# DIY_Keyboard_V1_1.net
KiCad netlist of a schematic drawn in EAGLE
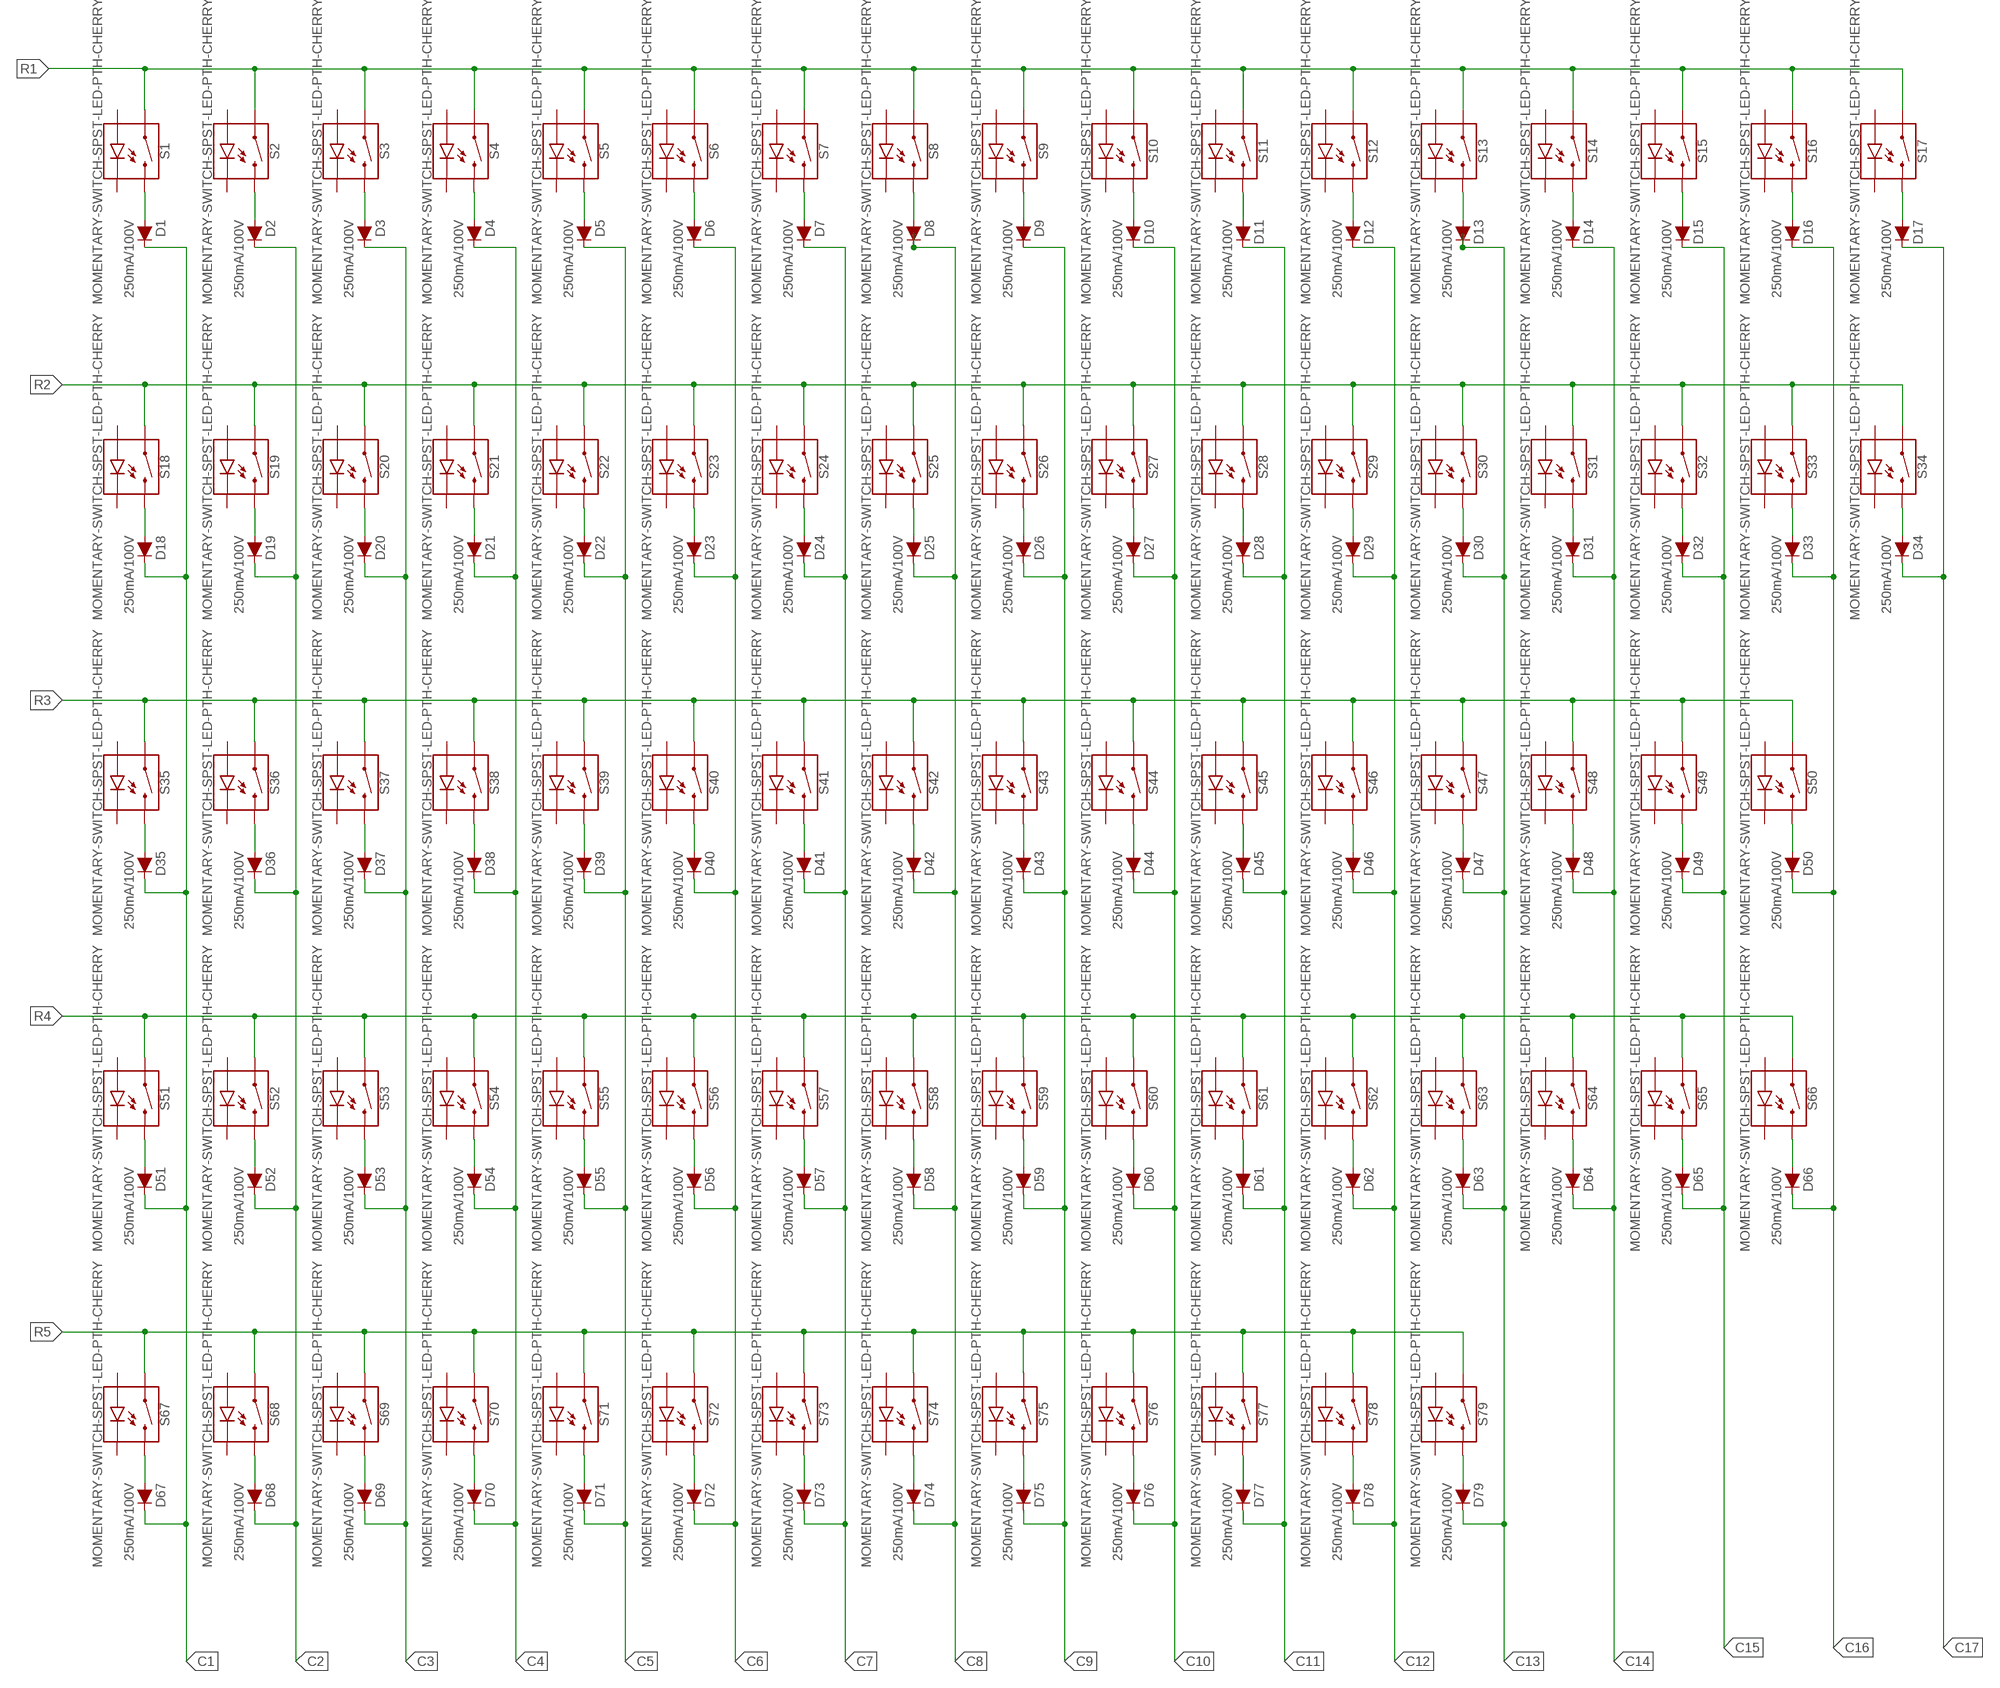
[diagram p0: schematic, sheet 1, part 1 of 2]
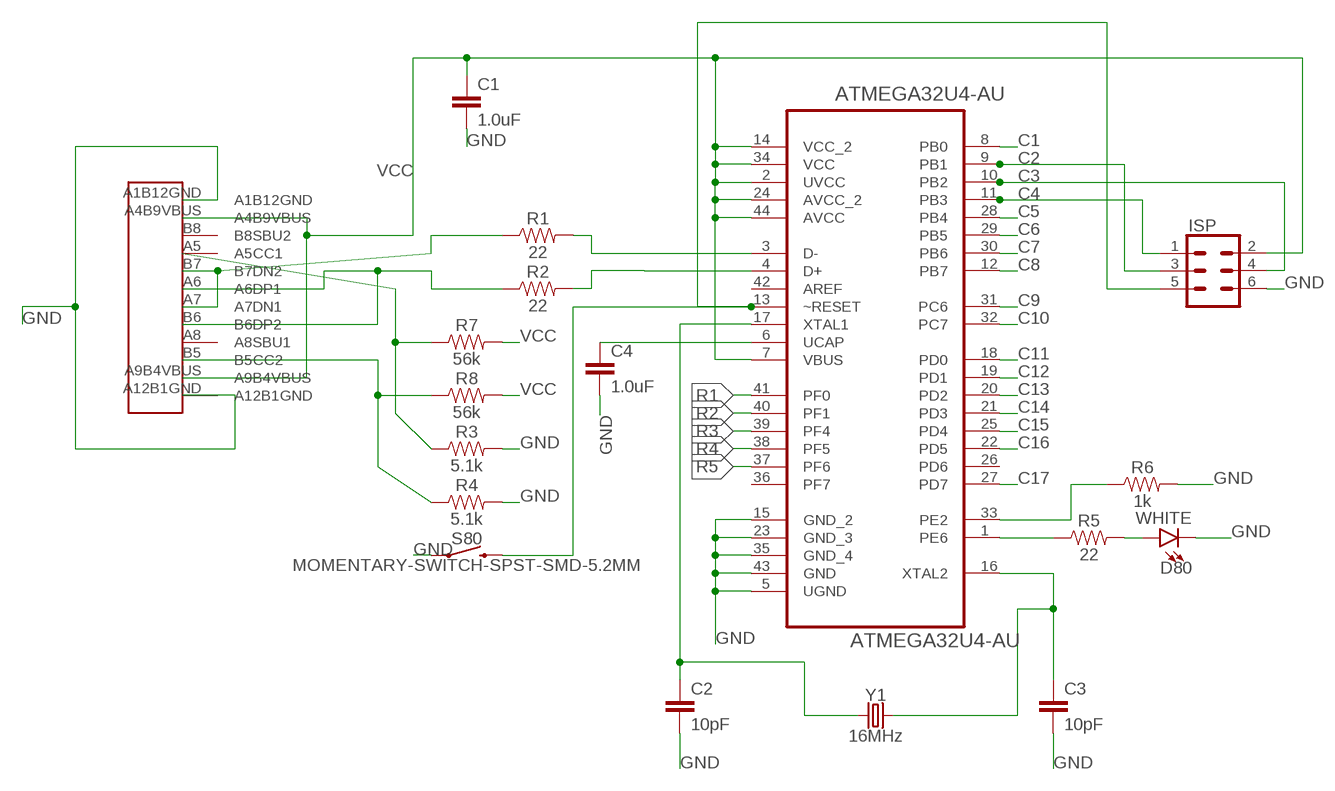
[diagram p1: schematic, sheet 1, part 2 of 2]

(export (version "E")
  (design (tool "Eeschema 10.0.6"))
  (components
    (comp (ref "ATMEGA32U4-AU")
      (value "ATMEGA32U4-AU")
      (footprint "eagle-import:QFP80P1200X1200X120-44N")
      (fields (field (name "MF") "Microchip"))
      (libsource (lib "eagle-import") (part "ATMEGA32U4-AU"))
    )
    (comp (ref "C1")
      (value "1.0uF")
      (footprint "eagle-import:0603")
      (libsource (lib "eagle-import") (part "1.0UF-0603-16V-10%"))
    )
    (comp (ref "C2")
      (value "10pF")
      (footprint "eagle-import:0603")
      (libsource (lib "eagle-import") (part "10PF-0603-50V-5%"))
    )
    (comp (ref "C3")
      (value "10pF")
      (footprint "eagle-import:0603")
      (libsource (lib "eagle-import") (part "10PF-0603-50V-5%"))
    )
    (comp (ref "C4")
      (value "1.0uF")
      (footprint "eagle-import:0603")
      (libsource (lib "eagle-import") (part "1.0UF-0603-16V-10%"))
    )
    (comp (ref "D1")
      (value "250mA/100V")
      (footprint "eagle-import:SOD-323")
      (libsource (lib "eagle-import") (part "DIODE-BAS16J"))
    )
    (comp (ref "D2")
      (value "250mA/100V")
      (footprint "eagle-import:SOD-323")
      (libsource (lib "eagle-import") (part "DIODE-BAS16J"))
    )
    (comp (ref "D3")
      (value "250mA/100V")
      (footprint "eagle-import:SOD-323")
      (libsource (lib "eagle-import") (part "DIODE-BAS16J"))
    )
    (comp (ref "D4")
      (value "250mA/100V")
      (footprint "eagle-import:SOD-323")
      (libsource (lib "eagle-import") (part "DIODE-BAS16J"))
    )
    (comp (ref "D5")
      (value "250mA/100V")
      (footprint "eagle-import:SOD-323")
      (libsource (lib "eagle-import") (part "DIODE-BAS16J"))
    )
    (comp (ref "D6")
      (value "250mA/100V")
      (footprint "eagle-import:SOD-323")
      (libsource (lib "eagle-import") (part "DIODE-BAS16J"))
    )
    (comp (ref "D7")
      (value "250mA/100V")
      (footprint "eagle-import:SOD-323")
      (libsource (lib "eagle-import") (part "DIODE-BAS16J"))
    )
    (comp (ref "D8")
      (value "250mA/100V")
      (footprint "eagle-import:SOD-323")
      (libsource (lib "eagle-import") (part "DIODE-BAS16J"))
    )
    (comp (ref "D9")
      (value "250mA/100V")
      (footprint "eagle-import:SOD-323")
      (libsource (lib "eagle-import") (part "DIODE-BAS16J"))
    )
    (comp (ref "D10")
      (value "250mA/100V")
      (footprint "eagle-import:SOD-323")
      (libsource (lib "eagle-import") (part "DIODE-BAS16J"))
    )
    (comp (ref "D11")
      (value "250mA/100V")
      (footprint "eagle-import:SOD-323")
      (libsource (lib "eagle-import") (part "DIODE-BAS16J"))
    )
    (comp (ref "D12")
      (value "250mA/100V")
      (footprint "eagle-import:SOD-323")
      (libsource (lib "eagle-import") (part "DIODE-BAS16J"))
    )
    (comp (ref "D13")
      (value "250mA/100V")
      (footprint "eagle-import:SOD-323")
      (libsource (lib "eagle-import") (part "DIODE-BAS16J"))
    )
    (comp (ref "D14")
      (value "250mA/100V")
      (footprint "eagle-import:SOD-323")
      (libsource (lib "eagle-import") (part "DIODE-BAS16J"))
    )
    (comp (ref "D15")
      (value "250mA/100V")
      (footprint "eagle-import:SOD-323")
      (libsource (lib "eagle-import") (part "DIODE-BAS16J"))
    )
    (comp (ref "D16")
      (value "250mA/100V")
      (footprint "eagle-import:SOD-323")
      (libsource (lib "eagle-import") (part "DIODE-BAS16J"))
    )
    (comp (ref "D17")
      (value "250mA/100V")
      (footprint "eagle-import:SOD-323")
      (libsource (lib "eagle-import") (part "DIODE-BAS16J"))
    )
    (comp (ref "D18")
      (value "250mA/100V")
      (footprint "eagle-import:SOD-323")
      (libsource (lib "eagle-import") (part "DIODE-BAS16J"))
    )
    (comp (ref "D19")
      (value "250mA/100V")
      (footprint "eagle-import:SOD-323")
      (libsource (lib "eagle-import") (part "DIODE-BAS16J"))
    )
    (comp (ref "D20")
      (value "250mA/100V")
      (footprint "eagle-import:SOD-323")
      (libsource (lib "eagle-import") (part "DIODE-BAS16J"))
    )
    (comp (ref "D21")
      (value "250mA/100V")
      (footprint "eagle-import:SOD-323")
      (libsource (lib "eagle-import") (part "DIODE-BAS16J"))
    )
    (comp (ref "D22")
      (value "250mA/100V")
      (footprint "eagle-import:SOD-323")
      (libsource (lib "eagle-import") (part "DIODE-BAS16J"))
    )
    (comp (ref "D23")
      (value "250mA/100V")
      (footprint "eagle-import:SOD-323")
      (libsource (lib "eagle-import") (part "DIODE-BAS16J"))
    )
    (comp (ref "D24")
      (value "250mA/100V")
      (footprint "eagle-import:SOD-323")
      (libsource (lib "eagle-import") (part "DIODE-BAS16J"))
    )
    (comp (ref "D25")
      (value "250mA/100V")
      (footprint "eagle-import:SOD-323")
      (libsource (lib "eagle-import") (part "DIODE-BAS16J"))
    )
    (comp (ref "D26")
      (value "250mA/100V")
      (footprint "eagle-import:SOD-323")
      (libsource (lib "eagle-import") (part "DIODE-BAS16J"))
    )
    (comp (ref "D27")
      (value "250mA/100V")
      (footprint "eagle-import:SOD-323")
      (libsource (lib "eagle-import") (part "DIODE-BAS16J"))
    )
    (comp (ref "D28")
      (value "250mA/100V")
      (footprint "eagle-import:SOD-323")
      (libsource (lib "eagle-import") (part "DIODE-BAS16J"))
    )
    (comp (ref "D29")
      (value "250mA/100V")
      (footprint "eagle-import:SOD-323")
      (libsource (lib "eagle-import") (part "DIODE-BAS16J"))
    )
    (comp (ref "D30")
      (value "250mA/100V")
      (footprint "eagle-import:SOD-323")
      (libsource (lib "eagle-import") (part "DIODE-BAS16J"))
    )
    (comp (ref "D31")
      (value "250mA/100V")
      (footprint "eagle-import:SOD-323")
      (libsource (lib "eagle-import") (part "DIODE-BAS16J"))
    )
    (comp (ref "D32")
      (value "250mA/100V")
      (footprint "eagle-import:SOD-323")
      (libsource (lib "eagle-import") (part "DIODE-BAS16J"))
    )
    (comp (ref "D33")
      (value "250mA/100V")
      (footprint "eagle-import:SOD-323")
      (libsource (lib "eagle-import") (part "DIODE-BAS16J"))
    )
    (comp (ref "D34")
      (value "250mA/100V")
      (footprint "eagle-import:SOD-323")
      (libsource (lib "eagle-import") (part "DIODE-BAS16J"))
    )
    (comp (ref "D35")
      (value "250mA/100V")
      (footprint "eagle-import:SOD-323")
      (libsource (lib "eagle-import") (part "DIODE-BAS16J"))
    )
    (comp (ref "D36")
      (value "250mA/100V")
      (footprint "eagle-import:SOD-323")
      (libsource (lib "eagle-import") (part "DIODE-BAS16J"))
    )
    (comp (ref "D37")
      (value "250mA/100V")
      (footprint "eagle-import:SOD-323")
      (libsource (lib "eagle-import") (part "DIODE-BAS16J"))
    )
    (comp (ref "D38")
      (value "250mA/100V")
      (footprint "eagle-import:SOD-323")
      (libsource (lib "eagle-import") (part "DIODE-BAS16J"))
    )
    (comp (ref "D39")
      (value "250mA/100V")
      (footprint "eagle-import:SOD-323")
      (libsource (lib "eagle-import") (part "DIODE-BAS16J"))
    )
    (comp (ref "D40")
      (value "250mA/100V")
      (footprint "eagle-import:SOD-323")
      (libsource (lib "eagle-import") (part "DIODE-BAS16J"))
    )
    (comp (ref "D41")
      (value "250mA/100V")
      (footprint "eagle-import:SOD-323")
      (libsource (lib "eagle-import") (part "DIODE-BAS16J"))
    )
    (comp (ref "D42")
      (value "250mA/100V")
      (footprint "eagle-import:SOD-323")
      (libsource (lib "eagle-import") (part "DIODE-BAS16J"))
    )
    (comp (ref "D43")
      (value "250mA/100V")
      (footprint "eagle-import:SOD-323")
      (libsource (lib "eagle-import") (part "DIODE-BAS16J"))
    )
    (comp (ref "D44")
      (value "250mA/100V")
      (footprint "eagle-import:SOD-323")
      (libsource (lib "eagle-import") (part "DIODE-BAS16J"))
    )
    (comp (ref "D45")
      (value "250mA/100V")
      (footprint "eagle-import:SOD-323")
      (libsource (lib "eagle-import") (part "DIODE-BAS16J"))
    )
    (comp (ref "D46")
      (value "250mA/100V")
      (footprint "eagle-import:SOD-323")
      (libsource (lib "eagle-import") (part "DIODE-BAS16J"))
    )
    (comp (ref "D47")
      (value "250mA/100V")
      (footprint "eagle-import:SOD-323")
      (libsource (lib "eagle-import") (part "DIODE-BAS16J"))
    )
    (comp (ref "D48")
      (value "250mA/100V")
      (footprint "eagle-import:SOD-323")
      (libsource (lib "eagle-import") (part "DIODE-BAS16J"))
    )
    (comp (ref "D49")
      (value "250mA/100V")
      (footprint "eagle-import:SOD-323")
      (libsource (lib "eagle-import") (part "DIODE-BAS16J"))
    )
    (comp (ref "D50")
      (value "250mA/100V")
      (footprint "eagle-import:SOD-323")
      (libsource (lib "eagle-import") (part "DIODE-BAS16J"))
    )
    (comp (ref "D51")
      (value "250mA/100V")
      (footprint "eagle-import:SOD-323")
      (libsource (lib "eagle-import") (part "DIODE-BAS16J"))
    )
    (comp (ref "D52")
      (value "250mA/100V")
      (footprint "eagle-import:SOD-323")
      (libsource (lib "eagle-import") (part "DIODE-BAS16J"))
    )
    (comp (ref "D53")
      (value "250mA/100V")
      (footprint "eagle-import:SOD-323")
      (libsource (lib "eagle-import") (part "DIODE-BAS16J"))
    )
    (comp (ref "D54")
      (value "250mA/100V")
      (footprint "eagle-import:SOD-323")
      (libsource (lib "eagle-import") (part "DIODE-BAS16J"))
    )
    (comp (ref "D55")
      (value "250mA/100V")
      (footprint "eagle-import:SOD-323")
      (libsource (lib "eagle-import") (part "DIODE-BAS16J"))
    )
    (comp (ref "D56")
      (value "250mA/100V")
      (footprint "eagle-import:SOD-323")
      (libsource (lib "eagle-import") (part "DIODE-BAS16J"))
    )
    (comp (ref "D57")
      (value "250mA/100V")
      (footprint "eagle-import:SOD-323")
      (libsource (lib "eagle-import") (part "DIODE-BAS16J"))
    )
    (comp (ref "D58")
      (value "250mA/100V")
      (footprint "eagle-import:SOD-323")
      (libsource (lib "eagle-import") (part "DIODE-BAS16J"))
    )
    (comp (ref "D59")
      (value "250mA/100V")
      (footprint "eagle-import:SOD-323")
      (libsource (lib "eagle-import") (part "DIODE-BAS16J"))
    )
    (comp (ref "D60")
      (value "250mA/100V")
      (footprint "eagle-import:SOD-323")
      (libsource (lib "eagle-import") (part "DIODE-BAS16J"))
    )
    (comp (ref "D61")
      (value "250mA/100V")
      (footprint "eagle-import:SOD-323")
      (libsource (lib "eagle-import") (part "DIODE-BAS16J"))
    )
    (comp (ref "D62")
      (value "250mA/100V")
      (footprint "eagle-import:SOD-323")
      (libsource (lib "eagle-import") (part "DIODE-BAS16J"))
    )
    (comp (ref "D63")
      (value "250mA/100V")
      (footprint "eagle-import:SOD-323")
      (libsource (lib "eagle-import") (part "DIODE-BAS16J"))
    )
    (comp (ref "D64")
      (value "250mA/100V")
      (footprint "eagle-import:SOD-323")
      (libsource (lib "eagle-import") (part "DIODE-BAS16J"))
    )
    (comp (ref "D65")
      (value "250mA/100V")
      (footprint "eagle-import:SOD-323")
      (libsource (lib "eagle-import") (part "DIODE-BAS16J"))
    )
    (comp (ref "D66")
      (value "250mA/100V")
      (footprint "eagle-import:SOD-323")
      (libsource (lib "eagle-import") (part "DIODE-BAS16J"))
    )
    (comp (ref "D67")
      (value "250mA/100V")
      (footprint "eagle-import:SOD-323")
      (libsource (lib "eagle-import") (part "DIODE-BAS16J"))
    )
    (comp (ref "D68")
      (value "250mA/100V")
      (footprint "eagle-import:SOD-323")
      (libsource (lib "eagle-import") (part "DIODE-BAS16J"))
    )
    (comp (ref "D69")
      (value "250mA/100V")
      (footprint "eagle-import:SOD-323")
      (libsource (lib "eagle-import") (part "DIODE-BAS16J"))
    )
    (comp (ref "D70")
      (value "250mA/100V")
      (footprint "eagle-import:SOD-323")
      (libsource (lib "eagle-import") (part "DIODE-BAS16J"))
    )
    (comp (ref "D71")
      (value "250mA/100V")
      (footprint "eagle-import:SOD-323")
      (libsource (lib "eagle-import") (part "DIODE-BAS16J"))
    )
    (comp (ref "D72")
      (value "250mA/100V")
      (footprint "eagle-import:SOD-323")
      (libsource (lib "eagle-import") (part "DIODE-BAS16J"))
    )
    (comp (ref "D73")
      (value "250mA/100V")
      (footprint "eagle-import:SOD-323")
      (libsource (lib "eagle-import") (part "DIODE-BAS16J"))
    )
    (comp (ref "D74")
      (value "250mA/100V")
      (footprint "eagle-import:SOD-323")
      (libsource (lib "eagle-import") (part "DIODE-BAS16J"))
    )
    (comp (ref "D75")
      (value "250mA/100V")
      (footprint "eagle-import:SOD-323")
      (libsource (lib "eagle-import") (part "DIODE-BAS16J"))
    )
    (comp (ref "D76")
      (value "250mA/100V")
      (footprint "eagle-import:SOD-323")
      (libsource (lib "eagle-import") (part "DIODE-BAS16J"))
    )
    (comp (ref "D77")
      (value "250mA/100V")
      (footprint "eagle-import:SOD-323")
      (libsource (lib "eagle-import") (part "DIODE-BAS16J"))
    )
    (comp (ref "D78")
      (value "250mA/100V")
      (footprint "eagle-import:SOD-323")
      (libsource (lib "eagle-import") (part "DIODE-BAS16J"))
    )
    (comp (ref "D79")
      (value "250mA/100V")
      (footprint "eagle-import:SOD-323")
      (libsource (lib "eagle-import") (part "DIODE-BAS16J"))
    )
    (comp (ref "D80")
      (value "WHITE")
      (footprint "eagle-import:LED-0603")
      (libsource (lib "eagle-import") (part "LED-WHITE0603"))
    )
    (comp (ref "ISP")
      (value "CONN_03X2FEMALE")
      (footprint "eagle-import:2X3")
      (libsource (lib "eagle-import") (part "CONN_03X2FEMALE"))
    )
    (comp (ref "R1")
      (value "22")
      (footprint "eagle-import:0603")
      (libsource (lib "eagle-import") (part "22OHM-0603-1/10W-1%"))
    )
    (comp (ref "R2")
      (value "22")
      (footprint "eagle-import:0603")
      (libsource (lib "eagle-import") (part "22OHM-0603-1/10W-1%"))
    )
    (comp (ref "R3")
      (value "5.1k")
      (footprint "eagle-import:0603")
      (libsource (lib "eagle-import") (part "56KOHM"))
    )
    (comp (ref "R4")
      (value "5.1k")
      (footprint "eagle-import:0603")
      (libsource (lib "eagle-import") (part "56KOHM"))
    )
    (comp (ref "R5")
      (value "22")
      (footprint "eagle-import:0603")
      (libsource (lib "eagle-import") (part "22OHM-0603-1/10W-1%"))
    )
    (comp (ref "R6")
      (value "1k")
      (footprint "eagle-import:0603")
      (libsource (lib "eagle-import") (part "1KOHM-0603-1/10W-1%"))
    )
    (comp (ref "R7")
      (value "56k")
      (footprint "eagle-import:0603")
      (libsource (lib "eagle-import") (part "56KOHM"))
    )
    (comp (ref "R8")
      (value "56k")
      (footprint "eagle-import:0603")
      (libsource (lib "eagle-import") (part "56KOHM"))
    )
    (comp (ref "S1")
      (value "MOMENTARY-SWITCH-SPST-LED-PTH-CHERRY")
      (footprint "eagle-import:CHERRY-MX-LED")
      (libsource (lib "eagle-import") (part "MOMENTARY-SWITCH-SPST-LED-PTH-CHERRY"))
    )
    (comp (ref "S2")
      (value "MOMENTARY-SWITCH-SPST-LED-PTH-CHERRY")
      (footprint "eagle-import:CHERRY-MX-LED")
      (libsource (lib "eagle-import") (part "MOMENTARY-SWITCH-SPST-LED-PTH-CHERRY"))
    )
    (comp (ref "S3")
      (value "MOMENTARY-SWITCH-SPST-LED-PTH-CHERRY")
      (footprint "eagle-import:CHERRY-MX-LED")
      (libsource (lib "eagle-import") (part "MOMENTARY-SWITCH-SPST-LED-PTH-CHERRY"))
    )
    (comp (ref "S4")
      (value "MOMENTARY-SWITCH-SPST-LED-PTH-CHERRY")
      (footprint "eagle-import:CHERRY-MX-LED")
      (libsource (lib "eagle-import") (part "MOMENTARY-SWITCH-SPST-LED-PTH-CHERRY"))
    )
    (comp (ref "S5")
      (value "MOMENTARY-SWITCH-SPST-LED-PTH-CHERRY")
      (footprint "eagle-import:CHERRY-MX-LED")
      (libsource (lib "eagle-import") (part "MOMENTARY-SWITCH-SPST-LED-PTH-CHERRY"))
    )
    (comp (ref "S6")
      (value "MOMENTARY-SWITCH-SPST-LED-PTH-CHERRY")
      (footprint "eagle-import:CHERRY-MX-LED")
      (libsource (lib "eagle-import") (part "MOMENTARY-SWITCH-SPST-LED-PTH-CHERRY"))
    )
    (comp (ref "S7")
      (value "MOMENTARY-SWITCH-SPST-LED-PTH-CHERRY")
      (footprint "eagle-import:CHERRY-MX-LED")
      (libsource (lib "eagle-import") (part "MOMENTARY-SWITCH-SPST-LED-PTH-CHERRY"))
    )
    (comp (ref "S8")
      (value "MOMENTARY-SWITCH-SPST-LED-PTH-CHERRY")
      (footprint "eagle-import:CHERRY-MX-LED")
      (libsource (lib "eagle-import") (part "MOMENTARY-SWITCH-SPST-LED-PTH-CHERRY"))
    )
    (comp (ref "S9")
      (value "MOMENTARY-SWITCH-SPST-LED-PTH-CHERRY")
      (footprint "eagle-import:CHERRY-MX-LED")
      (libsource (lib "eagle-import") (part "MOMENTARY-SWITCH-SPST-LED-PTH-CHERRY"))
    )
    (comp (ref "S10")
      (value "MOMENTARY-SWITCH-SPST-LED-PTH-CHERRY")
      (footprint "eagle-import:CHERRY-MX-LED")
      (libsource (lib "eagle-import") (part "MOMENTARY-SWITCH-SPST-LED-PTH-CHERRY"))
    )
    (comp (ref "S11")
      (value "MOMENTARY-SWITCH-SPST-LED-PTH-CHERRY")
      (footprint "eagle-import:CHERRY-MX-LED")
      (libsource (lib "eagle-import") (part "MOMENTARY-SWITCH-SPST-LED-PTH-CHERRY"))
    )
    (comp (ref "S12")
      (value "MOMENTARY-SWITCH-SPST-LED-PTH-CHERRY")
      (footprint "eagle-import:CHERRY-MX-LED")
      (libsource (lib "eagle-import") (part "MOMENTARY-SWITCH-SPST-LED-PTH-CHERRY"))
    )
    (comp (ref "S13")
      (value "MOMENTARY-SWITCH-SPST-LED-PTH-CHERRY")
      (footprint "eagle-import:CHERRY-MX-LED")
      (libsource (lib "eagle-import") (part "MOMENTARY-SWITCH-SPST-LED-PTH-CHERRY"))
    )
    (comp (ref "S14")
      (value "MOMENTARY-SWITCH-SPST-LED-PTH-CHERRY")
      (footprint "eagle-import:CHERRY-MX-LED")
      (libsource (lib "eagle-import") (part "MOMENTARY-SWITCH-SPST-LED-PTH-CHERRY"))
    )
    (comp (ref "S15")
      (value "MOMENTARY-SWITCH-SPST-LED-PTH-CHERRY")
      (footprint "eagle-import:CHERRY-MX-LED")
      (libsource (lib "eagle-import") (part "MOMENTARY-SWITCH-SPST-LED-PTH-CHERRY"))
    )
    (comp (ref "S16")
      (value "MOMENTARY-SWITCH-SPST-LED-PTH-CHERRY")
      (footprint "eagle-import:CHERRY-MX-LED")
      (libsource (lib "eagle-import") (part "MOMENTARY-SWITCH-SPST-LED-PTH-CHERRY"))
    )
    (comp (ref "S17")
      (value "MOMENTARY-SWITCH-SPST-LED-PTH-CHERRY")
      (footprint "eagle-import:CHERRY-MX-LED")
      (libsource (lib "eagle-import") (part "MOMENTARY-SWITCH-SPST-LED-PTH-CHERRY"))
    )
    (comp (ref "S18")
      (value "MOMENTARY-SWITCH-SPST-LED-PTH-CHERRY")
      (footprint "eagle-import:CHERRY-MX-LED")
      (libsource (lib "eagle-import") (part "MOMENTARY-SWITCH-SPST-LED-PTH-CHERRY"))
    )
    (comp (ref "S19")
      (value "MOMENTARY-SWITCH-SPST-LED-PTH-CHERRY")
      (footprint "eagle-import:CHERRY-MX-LED")
      (libsource (lib "eagle-import") (part "MOMENTARY-SWITCH-SPST-LED-PTH-CHERRY"))
    )
    (comp (ref "S20")
      (value "MOMENTARY-SWITCH-SPST-LED-PTH-CHERRY")
      (footprint "eagle-import:CHERRY-MX-LED")
      (libsource (lib "eagle-import") (part "MOMENTARY-SWITCH-SPST-LED-PTH-CHERRY"))
    )
    (comp (ref "S21")
      (value "MOMENTARY-SWITCH-SPST-LED-PTH-CHERRY")
      (footprint "eagle-import:CHERRY-MX-LED")
      (libsource (lib "eagle-import") (part "MOMENTARY-SWITCH-SPST-LED-PTH-CHERRY"))
    )
    (comp (ref "S22")
      (value "MOMENTARY-SWITCH-SPST-LED-PTH-CHERRY")
      (footprint "eagle-import:CHERRY-MX-LED")
      (libsource (lib "eagle-import") (part "MOMENTARY-SWITCH-SPST-LED-PTH-CHERRY"))
    )
    (comp (ref "S23")
      (value "MOMENTARY-SWITCH-SPST-LED-PTH-CHERRY")
      (footprint "eagle-import:CHERRY-MX-LED")
      (libsource (lib "eagle-import") (part "MOMENTARY-SWITCH-SPST-LED-PTH-CHERRY"))
    )
    (comp (ref "S24")
      (value "MOMENTARY-SWITCH-SPST-LED-PTH-CHERRY")
      (footprint "eagle-import:CHERRY-MX-LED")
      (libsource (lib "eagle-import") (part "MOMENTARY-SWITCH-SPST-LED-PTH-CHERRY"))
    )
    (comp (ref "S25")
      (value "MOMENTARY-SWITCH-SPST-LED-PTH-CHERRY")
      (footprint "eagle-import:CHERRY-MX-LED")
      (libsource (lib "eagle-import") (part "MOMENTARY-SWITCH-SPST-LED-PTH-CHERRY"))
    )
    (comp (ref "S26")
      (value "MOMENTARY-SWITCH-SPST-LED-PTH-CHERRY")
      (footprint "eagle-import:CHERRY-MX-LED")
      (libsource (lib "eagle-import") (part "MOMENTARY-SWITCH-SPST-LED-PTH-CHERRY"))
    )
    (comp (ref "S27")
      (value "MOMENTARY-SWITCH-SPST-LED-PTH-CHERRY")
      (footprint "eagle-import:CHERRY-MX-LED")
      (libsource (lib "eagle-import") (part "MOMENTARY-SWITCH-SPST-LED-PTH-CHERRY"))
    )
    (comp (ref "S28")
      (value "MOMENTARY-SWITCH-SPST-LED-PTH-CHERRY")
      (footprint "eagle-import:CHERRY-MX-LED")
      (libsource (lib "eagle-import") (part "MOMENTARY-SWITCH-SPST-LED-PTH-CHERRY"))
    )
    (comp (ref "S29")
      (value "MOMENTARY-SWITCH-SPST-LED-PTH-CHERRY")
      (footprint "eagle-import:CHERRY-MX-LED")
      (libsource (lib "eagle-import") (part "MOMENTARY-SWITCH-SPST-LED-PTH-CHERRY"))
    )
    (comp (ref "S30")
      (value "MOMENTARY-SWITCH-SPST-LED-PTH-CHERRY")
      (footprint "eagle-import:CHERRY-MX-LED")
      (libsource (lib "eagle-import") (part "MOMENTARY-SWITCH-SPST-LED-PTH-CHERRY"))
    )
    (comp (ref "S31")
      (value "MOMENTARY-SWITCH-SPST-LED-PTH-CHERRY")
      (footprint "eagle-import:CHERRY-MX-LED")
      (libsource (lib "eagle-import") (part "MOMENTARY-SWITCH-SPST-LED-PTH-CHERRY"))
    )
    (comp (ref "S32")
      (value "MOMENTARY-SWITCH-SPST-LED-PTH-CHERRY")
      (footprint "eagle-import:CHERRY-MX-LED")
      (libsource (lib "eagle-import") (part "MOMENTARY-SWITCH-SPST-LED-PTH-CHERRY"))
    )
    (comp (ref "S33")
      (value "MOMENTARY-SWITCH-SPST-LED-PTH-CHERRY")
      (footprint "eagle-import:CHERRY-MX-LED")
      (libsource (lib "eagle-import") (part "MOMENTARY-SWITCH-SPST-LED-PTH-CHERRY"))
    )
    (comp (ref "S34")
      (value "MOMENTARY-SWITCH-SPST-LED-PTH-CHERRY")
      (footprint "eagle-import:CHERRY-MX-LED")
      (libsource (lib "eagle-import") (part "MOMENTARY-SWITCH-SPST-LED-PTH-CHERRY"))
    )
    (comp (ref "S35")
      (value "MOMENTARY-SWITCH-SPST-LED-PTH-CHERRY")
      (footprint "eagle-import:CHERRY-MX-LED")
      (libsource (lib "eagle-import") (part "MOMENTARY-SWITCH-SPST-LED-PTH-CHERRY"))
    )
    (comp (ref "S36")
      (value "MOMENTARY-SWITCH-SPST-LED-PTH-CHERRY")
      (footprint "eagle-import:CHERRY-MX-LED")
      (libsource (lib "eagle-import") (part "MOMENTARY-SWITCH-SPST-LED-PTH-CHERRY"))
    )
    (comp (ref "S37")
      (value "MOMENTARY-SWITCH-SPST-LED-PTH-CHERRY")
      (footprint "eagle-import:CHERRY-MX-LED")
      (libsource (lib "eagle-import") (part "MOMENTARY-SWITCH-SPST-LED-PTH-CHERRY"))
    )
    (comp (ref "S38")
      (value "MOMENTARY-SWITCH-SPST-LED-PTH-CHERRY")
      (footprint "eagle-import:CHERRY-MX-LED")
      (libsource (lib "eagle-import") (part "MOMENTARY-SWITCH-SPST-LED-PTH-CHERRY"))
    )
    (comp (ref "S39")
      (value "MOMENTARY-SWITCH-SPST-LED-PTH-CHERRY")
      (footprint "eagle-import:CHERRY-MX-LED")
      (libsource (lib "eagle-import") (part "MOMENTARY-SWITCH-SPST-LED-PTH-CHERRY"))
    )
    (comp (ref "S40")
      (value "MOMENTARY-SWITCH-SPST-LED-PTH-CHERRY")
      (footprint "eagle-import:CHERRY-MX-LED")
      (libsource (lib "eagle-import") (part "MOMENTARY-SWITCH-SPST-LED-PTH-CHERRY"))
    )
    (comp (ref "S41")
      (value "MOMENTARY-SWITCH-SPST-LED-PTH-CHERRY")
      (footprint "eagle-import:CHERRY-MX-LED")
      (libsource (lib "eagle-import") (part "MOMENTARY-SWITCH-SPST-LED-PTH-CHERRY"))
    )
    (comp (ref "S42")
      (value "MOMENTARY-SWITCH-SPST-LED-PTH-CHERRY")
      (footprint "eagle-import:CHERRY-MX-LED")
      (libsource (lib "eagle-import") (part "MOMENTARY-SWITCH-SPST-LED-PTH-CHERRY"))
    )
    (comp (ref "S43")
      (value "MOMENTARY-SWITCH-SPST-LED-PTH-CHERRY")
      (footprint "eagle-import:CHERRY-MX-LED")
      (libsource (lib "eagle-import") (part "MOMENTARY-SWITCH-SPST-LED-PTH-CHERRY"))
    )
    (comp (ref "S44")
      (value "MOMENTARY-SWITCH-SPST-LED-PTH-CHERRY")
      (footprint "eagle-import:CHERRY-MX-LED")
      (libsource (lib "eagle-import") (part "MOMENTARY-SWITCH-SPST-LED-PTH-CHERRY"))
    )
    (comp (ref "S45")
      (value "MOMENTARY-SWITCH-SPST-LED-PTH-CHERRY")
      (footprint "eagle-import:CHERRY-MX-LED")
      (libsource (lib "eagle-import") (part "MOMENTARY-SWITCH-SPST-LED-PTH-CHERRY"))
    )
    (comp (ref "S46")
      (value "MOMENTARY-SWITCH-SPST-LED-PTH-CHERRY")
      (footprint "eagle-import:CHERRY-MX-LED")
      (libsource (lib "eagle-import") (part "MOMENTARY-SWITCH-SPST-LED-PTH-CHERRY"))
    )
    (comp (ref "S47")
      (value "MOMENTARY-SWITCH-SPST-LED-PTH-CHERRY")
      (footprint "eagle-import:CHERRY-MX-LED")
      (libsource (lib "eagle-import") (part "MOMENTARY-SWITCH-SPST-LED-PTH-CHERRY"))
    )
    (comp (ref "S48")
      (value "MOMENTARY-SWITCH-SPST-LED-PTH-CHERRY")
      (footprint "eagle-import:CHERRY-MX-LED")
      (libsource (lib "eagle-import") (part "MOMENTARY-SWITCH-SPST-LED-PTH-CHERRY"))
    )
    (comp (ref "S49")
      (value "MOMENTARY-SWITCH-SPST-LED-PTH-CHERRY")
      (footprint "eagle-import:CHERRY-MX-LED")
      (libsource (lib "eagle-import") (part "MOMENTARY-SWITCH-SPST-LED-PTH-CHERRY"))
    )
    (comp (ref "S50")
      (value "MOMENTARY-SWITCH-SPST-LED-PTH-CHERRY")
      (footprint "eagle-import:CHERRY-MX-LED")
      (libsource (lib "eagle-import") (part "MOMENTARY-SWITCH-SPST-LED-PTH-CHERRY"))
    )
    (comp (ref "S51")
      (value "MOMENTARY-SWITCH-SPST-LED-PTH-CHERRY")
      (footprint "eagle-import:CHERRY-MX-LED")
      (libsource (lib "eagle-import") (part "MOMENTARY-SWITCH-SPST-LED-PTH-CHERRY"))
    )
    (comp (ref "S52")
      (value "MOMENTARY-SWITCH-SPST-LED-PTH-CHERRY")
      (footprint "eagle-import:CHERRY-MX-LED")
      (libsource (lib "eagle-import") (part "MOMENTARY-SWITCH-SPST-LED-PTH-CHERRY"))
    )
    (comp (ref "S53")
      (value "MOMENTARY-SWITCH-SPST-LED-PTH-CHERRY")
      (footprint "eagle-import:CHERRY-MX-LED")
      (libsource (lib "eagle-import") (part "MOMENTARY-SWITCH-SPST-LED-PTH-CHERRY"))
    )
    (comp (ref "S54")
      (value "MOMENTARY-SWITCH-SPST-LED-PTH-CHERRY")
      (footprint "eagle-import:CHERRY-MX-LED")
      (libsource (lib "eagle-import") (part "MOMENTARY-SWITCH-SPST-LED-PTH-CHERRY"))
    )
    (comp (ref "S55")
      (value "MOMENTARY-SWITCH-SPST-LED-PTH-CHERRY")
      (footprint "eagle-import:CHERRY-MX-LED")
      (libsource (lib "eagle-import") (part "MOMENTARY-SWITCH-SPST-LED-PTH-CHERRY"))
    )
    (comp (ref "S56")
      (value "MOMENTARY-SWITCH-SPST-LED-PTH-CHERRY")
      (footprint "eagle-import:CHERRY-MX-LED")
      (libsource (lib "eagle-import") (part "MOMENTARY-SWITCH-SPST-LED-PTH-CHERRY"))
    )
    (comp (ref "S57")
      (value "MOMENTARY-SWITCH-SPST-LED-PTH-CHERRY")
      (footprint "eagle-import:CHERRY-MX-LED")
      (libsource (lib "eagle-import") (part "MOMENTARY-SWITCH-SPST-LED-PTH-CHERRY"))
    )
    (comp (ref "S58")
      (value "MOMENTARY-SWITCH-SPST-LED-PTH-CHERRY")
      (footprint "eagle-import:CHERRY-MX-LED")
      (libsource (lib "eagle-import") (part "MOMENTARY-SWITCH-SPST-LED-PTH-CHERRY"))
    )
    (comp (ref "S59")
      (value "MOMENTARY-SWITCH-SPST-LED-PTH-CHERRY")
      (footprint "eagle-import:CHERRY-MX-LED")
      (libsource (lib "eagle-import") (part "MOMENTARY-SWITCH-SPST-LED-PTH-CHERRY"))
    )
    (comp (ref "S60")
      (value "MOMENTARY-SWITCH-SPST-LED-PTH-CHERRY")
      (footprint "eagle-import:CHERRY-MX-LED")
      (libsource (lib "eagle-import") (part "MOMENTARY-SWITCH-SPST-LED-PTH-CHERRY"))
    )
    (comp (ref "S61")
      (value "MOMENTARY-SWITCH-SPST-LED-PTH-CHERRY")
      (footprint "eagle-import:CHERRY-MX-LED")
      (libsource (lib "eagle-import") (part "MOMENTARY-SWITCH-SPST-LED-PTH-CHERRY"))
    )
    (comp (ref "S62")
      (value "MOMENTARY-SWITCH-SPST-LED-PTH-CHERRY")
      (footprint "eagle-import:CHERRY-MX-LED")
      (libsource (lib "eagle-import") (part "MOMENTARY-SWITCH-SPST-LED-PTH-CHERRY"))
    )
    (comp (ref "S63")
      (value "MOMENTARY-SWITCH-SPST-LED-PTH-CHERRY")
      (footprint "eagle-import:CHERRY-MX-LED")
      (libsource (lib "eagle-import") (part "MOMENTARY-SWITCH-SPST-LED-PTH-CHERRY"))
    )
    (comp (ref "S64")
      (value "MOMENTARY-SWITCH-SPST-LED-PTH-CHERRY")
      (footprint "eagle-import:CHERRY-MX-LED")
      (libsource (lib "eagle-import") (part "MOMENTARY-SWITCH-SPST-LED-PTH-CHERRY"))
    )
    (comp (ref "S65")
      (value "MOMENTARY-SWITCH-SPST-LED-PTH-CHERRY")
      (footprint "eagle-import:CHERRY-MX-LED")
      (libsource (lib "eagle-import") (part "MOMENTARY-SWITCH-SPST-LED-PTH-CHERRY"))
    )
    (comp (ref "S66")
      (value "MOMENTARY-SWITCH-SPST-LED-PTH-CHERRY")
      (footprint "eagle-import:CHERRY-MX-LED")
      (libsource (lib "eagle-import") (part "MOMENTARY-SWITCH-SPST-LED-PTH-CHERRY"))
    )
    (comp (ref "S67")
      (value "MOMENTARY-SWITCH-SPST-LED-PTH-CHERRY")
      (footprint "eagle-import:CHERRY-MX-LED")
      (libsource (lib "eagle-import") (part "MOMENTARY-SWITCH-SPST-LED-PTH-CHERRY"))
    )
    (comp (ref "S68")
      (value "MOMENTARY-SWITCH-SPST-LED-PTH-CHERRY")
      (footprint "eagle-import:CHERRY-MX-LED")
      (libsource (lib "eagle-import") (part "MOMENTARY-SWITCH-SPST-LED-PTH-CHERRY"))
    )
    (comp (ref "S69")
      (value "MOMENTARY-SWITCH-SPST-LED-PTH-CHERRY")
      (footprint "eagle-import:CHERRY-MX-LED")
      (libsource (lib "eagle-import") (part "MOMENTARY-SWITCH-SPST-LED-PTH-CHERRY"))
    )
    (comp (ref "S70")
      (value "MOMENTARY-SWITCH-SPST-LED-PTH-CHERRY")
      (footprint "eagle-import:CHERRY-MX-LED")
      (libsource (lib "eagle-import") (part "MOMENTARY-SWITCH-SPST-LED-PTH-CHERRY"))
    )
    (comp (ref "S71")
      (value "MOMENTARY-SWITCH-SPST-LED-PTH-CHERRY")
      (footprint "eagle-import:CHERRY-MX-LED")
      (libsource (lib "eagle-import") (part "MOMENTARY-SWITCH-SPST-LED-PTH-CHERRY"))
    )
    (comp (ref "S72")
      (value "MOMENTARY-SWITCH-SPST-LED-PTH-CHERRY")
      (footprint "eagle-import:CHERRY-MX-LED")
      (libsource (lib "eagle-import") (part "MOMENTARY-SWITCH-SPST-LED-PTH-CHERRY"))
    )
    (comp (ref "S73")
      (value "MOMENTARY-SWITCH-SPST-LED-PTH-CHERRY")
      (footprint "eagle-import:CHERRY-MX-LED")
      (libsource (lib "eagle-import") (part "MOMENTARY-SWITCH-SPST-LED-PTH-CHERRY"))
    )
    (comp (ref "S74")
      (value "MOMENTARY-SWITCH-SPST-LED-PTH-CHERRY")
      (footprint "eagle-import:CHERRY-MX-LED")
      (libsource (lib "eagle-import") (part "MOMENTARY-SWITCH-SPST-LED-PTH-CHERRY"))
    )
    (comp (ref "S75")
      (value "MOMENTARY-SWITCH-SPST-LED-PTH-CHERRY")
      (footprint "eagle-import:CHERRY-MX-LED")
      (libsource (lib "eagle-import") (part "MOMENTARY-SWITCH-SPST-LED-PTH-CHERRY"))
    )
    (comp (ref "S76")
      (value "MOMENTARY-SWITCH-SPST-LED-PTH-CHERRY")
      (footprint "eagle-import:CHERRY-MX-LED")
      (libsource (lib "eagle-import") (part "MOMENTARY-SWITCH-SPST-LED-PTH-CHERRY"))
    )
    (comp (ref "S77")
      (value "MOMENTARY-SWITCH-SPST-LED-PTH-CHERRY")
      (footprint "eagle-import:CHERRY-MX-LED")
      (libsource (lib "eagle-import") (part "MOMENTARY-SWITCH-SPST-LED-PTH-CHERRY"))
    )
    (comp (ref "S78")
      (value "MOMENTARY-SWITCH-SPST-LED-PTH-CHERRY")
      (footprint "eagle-import:CHERRY-MX-LED")
      (libsource (lib "eagle-import") (part "MOMENTARY-SWITCH-SPST-LED-PTH-CHERRY"))
    )
    (comp (ref "S79")
      (value "MOMENTARY-SWITCH-SPST-LED-PTH-CHERRY")
      (footprint "eagle-import:CHERRY-MX-LED")
      (libsource (lib "eagle-import") (part "MOMENTARY-SWITCH-SPST-LED-PTH-CHERRY"))
    )
    (comp (ref "S80")
      (value "MOMENTARY-SWITCH-SPST-SMD-5.2MM")
      (footprint "eagle-import:TACTILE_SWITCH_SMD_5.2MM")
      (libsource (lib "eagle-import") (part "MOMENTARY-SWITCH-SPST-SMD-5.2MM"))
    )
    (comp (ref "U$1")
      (value "USB_TYPE_C")
      (footprint "eagle-import:USB_TYPE_C")
      (libsource (lib "eagle-import") (part "USB_TYPE_C"))
    )
    (comp (ref "Y1")
      (value "16MHz")
      (footprint "eagle-import:CRYSTAL-SMD-5X3.2-4PAD")
      (libsource (lib "eagle-import") (part "CRYSTAL-16MHZSMD-5X3.2"))
    )
  )
  (nets
    (net (code "1") (name "/GND") (class "Default")
      (node (ref "ATMEGA32U4-AU") (pin "15") (pinfunction "GND_2_15") (pintype "passive"))
      (node (ref "ATMEGA32U4-AU") (pin "23") (pinfunction "GND_3_23") (pintype "passive"))
      (node (ref "ATMEGA32U4-AU") (pin "35") (pinfunction "GND_4_35") (pintype "passive"))
      (node (ref "ATMEGA32U4-AU") (pin "43") (pinfunction "GND_43") (pintype "passive"))
      (node (ref "ATMEGA32U4-AU") (pin "5") (pinfunction "UGND_5") (pintype "passive"))
      (node (ref "C1") (pin "2") (pinfunction "2_2") (pintype "passive"))
      (node (ref "C2") (pin "2") (pinfunction "2_2") (pintype "passive"))
      (node (ref "C3") (pin "2") (pinfunction "2_2") (pintype "passive"))
      (node (ref "C4") (pin "2") (pinfunction "2_2") (pintype "passive"))
      (node (ref "D80") (pin "C") (pinfunction "C_C") (pintype "passive"))
      (node (ref "ISP") (pin "6") (pinfunction "6_6") (pintype "bidirectional"))
      (node (ref "R3") (pin "2") (pinfunction "2_2") (pintype "passive"))
      (node (ref "R4") (pin "2") (pinfunction "2_2") (pintype "passive"))
      (node (ref "R6") (pin "2") (pinfunction "2_2") (pintype "passive"))
      (node (ref "S80") (pin "1") (pinfunction "1_1") (pintype "passive"))
      (node (ref "U$1") (pin "A12B1GND") (pinfunction "A12B1GND_A12B1GND") (pintype "bidirectional"))
      (node (ref "U$1") (pin "A1B12GND") (pinfunction "A1B12GND_A1B12GND") (pintype "bidirectional"))
    )
    (net (code "2") (name "/VCC") (class "Default")
      (node (ref "ATMEGA32U4-AU") (pin "14") (pinfunction "VCC_2_14") (pintype "power_in"))
      (node (ref "ATMEGA32U4-AU") (pin "2") (pinfunction "UVCC_2") (pintype "power_in"))
      (node (ref "ATMEGA32U4-AU") (pin "24") (pinfunction "AVCC_2_24") (pintype "power_in"))
      (node (ref "ATMEGA32U4-AU") (pin "34") (pinfunction "VCC_34") (pintype "power_in"))
      (node (ref "ATMEGA32U4-AU") (pin "44") (pinfunction "AVCC_44") (pintype "power_in"))
      (node (ref "ATMEGA32U4-AU") (pin "7") (pinfunction "VBUS_7") (pintype "input"))
      (node (ref "C1") (pin "1") (pinfunction "1_1") (pintype "passive"))
      (node (ref "ISP") (pin "2") (pinfunction "2_2") (pintype "bidirectional"))
      (node (ref "R7") (pin "2") (pinfunction "2_2") (pintype "passive"))
      (node (ref "R8") (pin "2") (pinfunction "2_2") (pintype "passive"))
      (node (ref "U$1") (pin "A4B9VBUS") (pinfunction "A4B9VBUS_A4B9VBUS") (pintype "bidirectional"))
      (node (ref "U$1") (pin "A9B4VBUS") (pinfunction "A9B4VBUS_A9B4VBUS") (pintype "bidirectional"))
    )
    (net (code "3") (name "C1") (class "Default")
      (node (ref "ATMEGA32U4-AU") (pin "8") (pinfunction "PB0_8") (pintype "bidirectional"))
      (node (ref "D1") (pin "C") (pinfunction "C_C") (pintype "passive"))
      (node (ref "D18") (pin "C") (pinfunction "C_C") (pintype "passive"))
      (node (ref "D35") (pin "C") (pinfunction "C_C") (pintype "passive"))
      (node (ref "D51") (pin "C") (pinfunction "C_C") (pintype "passive"))
      (node (ref "D67") (pin "C") (pinfunction "C_C") (pintype "passive"))
    )
    (net (code "4") (name "C2") (class "Default")
      (node (ref "ATMEGA32U4-AU") (pin "9") (pinfunction "PB1_9") (pintype "bidirectional"))
      (node (ref "D19") (pin "C") (pinfunction "C_C") (pintype "passive"))
      (node (ref "D2") (pin "C") (pinfunction "C_C") (pintype "passive"))
      (node (ref "D36") (pin "C") (pinfunction "C_C") (pintype "passive"))
      (node (ref "D52") (pin "C") (pinfunction "C_C") (pintype "passive"))
      (node (ref "D68") (pin "C") (pinfunction "C_C") (pintype "passive"))
      (node (ref "ISP") (pin "3") (pinfunction "3_3") (pintype "bidirectional"))
    )
    (net (code "5") (name "C3") (class "Default")
      (node (ref "ATMEGA32U4-AU") (pin "10") (pinfunction "PB2_10") (pintype "bidirectional"))
      (node (ref "D20") (pin "C") (pinfunction "C_C") (pintype "passive"))
      (node (ref "D3") (pin "C") (pinfunction "C_C") (pintype "passive"))
      (node (ref "D37") (pin "C") (pinfunction "C_C") (pintype "passive"))
      (node (ref "D53") (pin "C") (pinfunction "C_C") (pintype "passive"))
      (node (ref "D69") (pin "C") (pinfunction "C_C") (pintype "passive"))
      (node (ref "ISP") (pin "4") (pinfunction "4_4") (pintype "bidirectional"))
    )
    (net (code "6") (name "C4") (class "Default")
      (node (ref "ATMEGA32U4-AU") (pin "11") (pinfunction "PB3_11") (pintype "bidirectional"))
      (node (ref "D21") (pin "C") (pinfunction "C_C") (pintype "passive"))
      (node (ref "D38") (pin "C") (pinfunction "C_C") (pintype "passive"))
      (node (ref "D4") (pin "C") (pinfunction "C_C") (pintype "passive"))
      (node (ref "D54") (pin "C") (pinfunction "C_C") (pintype "passive"))
      (node (ref "D70") (pin "C") (pinfunction "C_C") (pintype "passive"))
      (node (ref "ISP") (pin "1") (pinfunction "1_1") (pintype "bidirectional"))
    )
    (net (code "7") (name "C5") (class "Default")
      (node (ref "ATMEGA32U4-AU") (pin "28") (pinfunction "PB4_28") (pintype "bidirectional"))
      (node (ref "D22") (pin "C") (pinfunction "C_C") (pintype "passive"))
      (node (ref "D39") (pin "C") (pinfunction "C_C") (pintype "passive"))
      (node (ref "D5") (pin "C") (pinfunction "C_C") (pintype "passive"))
      (node (ref "D55") (pin "C") (pinfunction "C_C") (pintype "passive"))
      (node (ref "D71") (pin "C") (pinfunction "C_C") (pintype "passive"))
    )
    (net (code "8") (name "C6") (class "Default")
      (node (ref "ATMEGA32U4-AU") (pin "29") (pinfunction "PB5_29") (pintype "bidirectional"))
      (node (ref "D23") (pin "C") (pinfunction "C_C") (pintype "passive"))
      (node (ref "D40") (pin "C") (pinfunction "C_C") (pintype "passive"))
      (node (ref "D56") (pin "C") (pinfunction "C_C") (pintype "passive"))
      (node (ref "D6") (pin "C") (pinfunction "C_C") (pintype "passive"))
      (node (ref "D72") (pin "C") (pinfunction "C_C") (pintype "passive"))
    )
    (net (code "9") (name "C7") (class "Default")
      (node (ref "ATMEGA32U4-AU") (pin "30") (pinfunction "PB6_30") (pintype "bidirectional"))
      (node (ref "D24") (pin "C") (pinfunction "C_C") (pintype "passive"))
      (node (ref "D41") (pin "C") (pinfunction "C_C") (pintype "passive"))
      (node (ref "D57") (pin "C") (pinfunction "C_C") (pintype "passive"))
      (node (ref "D7") (pin "C") (pinfunction "C_C") (pintype "passive"))
      (node (ref "D73") (pin "C") (pinfunction "C_C") (pintype "passive"))
    )
    (net (code "10") (name "C8") (class "Default")
      (node (ref "ATMEGA32U4-AU") (pin "12") (pinfunction "PB7_12") (pintype "bidirectional"))
      (node (ref "D25") (pin "C") (pinfunction "C_C") (pintype "passive"))
      (node (ref "D42") (pin "C") (pinfunction "C_C") (pintype "passive"))
      (node (ref "D58") (pin "C") (pinfunction "C_C") (pintype "passive"))
      (node (ref "D74") (pin "C") (pinfunction "C_C") (pintype "passive"))
      (node (ref "D8") (pin "C") (pinfunction "C_C") (pintype "passive"))
    )
    (net (code "11") (name "C9") (class "Default")
      (node (ref "ATMEGA32U4-AU") (pin "31") (pinfunction "PC6_31") (pintype "bidirectional"))
      (node (ref "D26") (pin "C") (pinfunction "C_C") (pintype "passive"))
      (node (ref "D43") (pin "C") (pinfunction "C_C") (pintype "passive"))
      (node (ref "D59") (pin "C") (pinfunction "C_C") (pintype "passive"))
      (node (ref "D75") (pin "C") (pinfunction "C_C") (pintype "passive"))
      (node (ref "D9") (pin "C") (pinfunction "C_C") (pintype "passive"))
    )
    (net (code "12") (name "C10") (class "Default")
      (node (ref "ATMEGA32U4-AU") (pin "32") (pinfunction "PC7_32") (pintype "bidirectional"))
      (node (ref "D10") (pin "C") (pinfunction "C_C") (pintype "passive"))
      (node (ref "D27") (pin "C") (pinfunction "C_C") (pintype "passive"))
      (node (ref "D44") (pin "C") (pinfunction "C_C") (pintype "passive"))
      (node (ref "D60") (pin "C") (pinfunction "C_C") (pintype "passive"))
      (node (ref "D76") (pin "C") (pinfunction "C_C") (pintype "passive"))
    )
    (net (code "13") (name "C11") (class "Default")
      (node (ref "ATMEGA32U4-AU") (pin "18") (pinfunction "PD0_18") (pintype "bidirectional"))
      (node (ref "D11") (pin "C") (pinfunction "C_C") (pintype "passive"))
      (node (ref "D28") (pin "C") (pinfunction "C_C") (pintype "passive"))
      (node (ref "D45") (pin "C") (pinfunction "C_C") (pintype "passive"))
      (node (ref "D61") (pin "C") (pinfunction "C_C") (pintype "passive"))
      (node (ref "D77") (pin "C") (pinfunction "C_C") (pintype "passive"))
    )
    (net (code "14") (name "C12") (class "Default")
      (node (ref "ATMEGA32U4-AU") (pin "19") (pinfunction "PD1_19") (pintype "bidirectional"))
      (node (ref "D12") (pin "C") (pinfunction "C_C") (pintype "passive"))
      (node (ref "D29") (pin "C") (pinfunction "C_C") (pintype "passive"))
      (node (ref "D46") (pin "C") (pinfunction "C_C") (pintype "passive"))
      (node (ref "D62") (pin "C") (pinfunction "C_C") (pintype "passive"))
      (node (ref "D78") (pin "C") (pinfunction "C_C") (pintype "passive"))
    )
    (net (code "15") (name "C13") (class "Default")
      (node (ref "ATMEGA32U4-AU") (pin "20") (pinfunction "PD2_20") (pintype "bidirectional"))
      (node (ref "D13") (pin "C") (pinfunction "C_C") (pintype "passive"))
      (node (ref "D30") (pin "C") (pinfunction "C_C") (pintype "passive"))
      (node (ref "D47") (pin "C") (pinfunction "C_C") (pintype "passive"))
      (node (ref "D63") (pin "C") (pinfunction "C_C") (pintype "passive"))
      (node (ref "D79") (pin "C") (pinfunction "C_C") (pintype "passive"))
    )
    (net (code "16") (name "C14") (class "Default")
      (node (ref "ATMEGA32U4-AU") (pin "21") (pinfunction "PD3_21") (pintype "bidirectional"))
      (node (ref "D14") (pin "C") (pinfunction "C_C") (pintype "passive"))
      (node (ref "D31") (pin "C") (pinfunction "C_C") (pintype "passive"))
      (node (ref "D48") (pin "C") (pinfunction "C_C") (pintype "passive"))
      (node (ref "D64") (pin "C") (pinfunction "C_C") (pintype "passive"))
    )
    (net (code "17") (name "C15") (class "Default")
      (node (ref "ATMEGA32U4-AU") (pin "25") (pinfunction "PD4_25") (pintype "bidirectional"))
      (node (ref "D15") (pin "C") (pinfunction "C_C") (pintype "passive"))
      (node (ref "D32") (pin "C") (pinfunction "C_C") (pintype "passive"))
      (node (ref "D49") (pin "C") (pinfunction "C_C") (pintype "passive"))
      (node (ref "D65") (pin "C") (pinfunction "C_C") (pintype "passive"))
    )
    (net (code "18") (name "C16") (class "Default")
      (node (ref "ATMEGA32U4-AU") (pin "22") (pinfunction "PD5_22") (pintype "bidirectional"))
      (node (ref "D16") (pin "C") (pinfunction "C_C") (pintype "passive"))
      (node (ref "D33") (pin "C") (pinfunction "C_C") (pintype "passive"))
      (node (ref "D50") (pin "C") (pinfunction "C_C") (pintype "passive"))
      (node (ref "D66") (pin "C") (pinfunction "C_C") (pintype "passive"))
    )
    (net (code "19") (name "C17") (class "Default")
      (node (ref "ATMEGA32U4-AU") (pin "27") (pinfunction "PD7_27") (pintype "bidirectional"))
      (node (ref "D17") (pin "C") (pinfunction "C_C") (pintype "passive"))
      (node (ref "D34") (pin "C") (pinfunction "C_C") (pintype "passive"))
    )
    (net (code "20") (name "Net-(ATMEGA32U4-AU-D+)") (class "Default")
      (node (ref "ATMEGA32U4-AU") (pin "4") (pinfunction "D+_4") (pintype "passive"))
      (node (ref "R2") (pin "2") (pinfunction "2_2") (pintype "passive"))
    )
    (net (code "21") (name "Net-(ATMEGA32U4-AU-D-)") (class "Default")
      (node (ref "ATMEGA32U4-AU") (pin "3") (pinfunction "D-_3") (pintype "passive"))
      (node (ref "R1") (pin "2") (pinfunction "2_2") (pintype "passive"))
    )
    (net (code "22") (name "Net-(ATMEGA32U4-AU-PE2)") (class "Default")
      (node (ref "ATMEGA32U4-AU") (pin "33") (pinfunction "PE2_33") (pintype "bidirectional"))
      (node (ref "R6") (pin "1") (pinfunction "1_1") (pintype "passive"))
    )
    (net (code "23") (name "Net-(ATMEGA32U4-AU-PE6)") (class "Default")
      (node (ref "ATMEGA32U4-AU") (pin "1") (pinfunction "PE6_1") (pintype "bidirectional"))
      (node (ref "R5") (pin "1") (pinfunction "1_1") (pintype "passive"))
    )
    (net (code "24") (name "Net-(ATMEGA32U4-AU-UCAP)") (class "Default")
      (node (ref "ATMEGA32U4-AU") (pin "6") (pinfunction "UCAP_6") (pintype "power_in"))
      (node (ref "C4") (pin "1") (pinfunction "1_1") (pintype "passive"))
    )
    (net (code "25") (name "Net-(ATMEGA32U4-AU-XTAL1)") (class "Default")
      (node (ref "ATMEGA32U4-AU") (pin "17") (pinfunction "XTAL1_17") (pintype "input"))
      (node (ref "C2") (pin "1") (pinfunction "1_1") (pintype "passive"))
      (node (ref "Y1") (pin "1") (pinfunction "1_1") (pintype "passive"))
    )
    (net (code "26") (name "Net-(ATMEGA32U4-AU-XTAL2)") (class "Default")
      (node (ref "ATMEGA32U4-AU") (pin "16") (pinfunction "XTAL2_16") (pintype "output"))
      (node (ref "C3") (pin "1") (pinfunction "1_1") (pintype "passive"))
      (node (ref "Y1") (pin "3") (pinfunction "2_3") (pintype "passive"))
    )
    (net (code "27") (name "Net-(ATMEGA32U4-AU-~{RESET})") (class "Default")
      (node (ref "ATMEGA32U4-AU") (pin "13") (pinfunction "~{RESET}_13") (pintype "input"))
      (node (ref "ISP") (pin "5") (pinfunction "5_5") (pintype "bidirectional"))
      (node (ref "S80") (pin "3") (pinfunction "2_3") (pintype "passive"))
    )
    (net (code "28") (name "Net-(D80-PadA)") (class "Default")
      (node (ref "D80") (pin "A") (pinfunction "A_A") (pintype "passive"))
      (node (ref "R5") (pin "2") (pinfunction "2_2") (pintype "passive"))
    )
    (net (code "29") (name "Net-(S1-2)") (class "Default")
      (node (ref "D1") (pin "A") (pinfunction "A_A") (pintype "passive"))
      (node (ref "S1") (pin "S2") (pinfunction "2_S2") (pintype "passive"))
    )
    (net (code "30") (name "Net-(S2-2)") (class "Default")
      (node (ref "D2") (pin "A") (pinfunction "A_A") (pintype "passive"))
      (node (ref "S2") (pin "S2") (pinfunction "2_S2") (pintype "passive"))
    )
    (net (code "31") (name "Net-(S3-2)") (class "Default")
      (node (ref "D3") (pin "A") (pinfunction "A_A") (pintype "passive"))
      (node (ref "S3") (pin "S2") (pinfunction "2_S2") (pintype "passive"))
    )
    (net (code "32") (name "Net-(S4-2)") (class "Default")
      (node (ref "D4") (pin "A") (pinfunction "A_A") (pintype "passive"))
      (node (ref "S4") (pin "S2") (pinfunction "2_S2") (pintype "passive"))
    )
    (net (code "33") (name "Net-(S5-2)") (class "Default")
      (node (ref "D5") (pin "A") (pinfunction "A_A") (pintype "passive"))
      (node (ref "S5") (pin "S2") (pinfunction "2_S2") (pintype "passive"))
    )
    (net (code "34") (name "Net-(S6-2)") (class "Default")
      (node (ref "D6") (pin "A") (pinfunction "A_A") (pintype "passive"))
      (node (ref "S6") (pin "S2") (pinfunction "2_S2") (pintype "passive"))
    )
    (net (code "35") (name "Net-(S7-2)") (class "Default")
      (node (ref "D7") (pin "A") (pinfunction "A_A") (pintype "passive"))
      (node (ref "S7") (pin "S2") (pinfunction "2_S2") (pintype "passive"))
    )
    (net (code "36") (name "Net-(S8-2)") (class "Default")
      (node (ref "D8") (pin "A") (pinfunction "A_A") (pintype "passive"))
      (node (ref "S8") (pin "S2") (pinfunction "2_S2") (pintype "passive"))
    )
    (net (code "37") (name "Net-(S9-2)") (class "Default")
      (node (ref "D9") (pin "A") (pinfunction "A_A") (pintype "passive"))
      (node (ref "S9") (pin "S2") (pinfunction "2_S2") (pintype "passive"))
    )
    (net (code "38") (name "Net-(S10-2)") (class "Default")
      (node (ref "D10") (pin "A") (pinfunction "A_A") (pintype "passive"))
      (node (ref "S10") (pin "S2") (pinfunction "2_S2") (pintype "passive"))
    )
    (net (code "39") (name "Net-(S11-2)") (class "Default")
      (node (ref "D11") (pin "A") (pinfunction "A_A") (pintype "passive"))
      (node (ref "S11") (pin "S2") (pinfunction "2_S2") (pintype "passive"))
    )
    (net (code "40") (name "Net-(S12-2)") (class "Default")
      (node (ref "D12") (pin "A") (pinfunction "A_A") (pintype "passive"))
      (node (ref "S12") (pin "S2") (pinfunction "2_S2") (pintype "passive"))
    )
    (net (code "41") (name "Net-(S13-2)") (class "Default")
      (node (ref "D13") (pin "A") (pinfunction "A_A") (pintype "passive"))
      (node (ref "S13") (pin "S2") (pinfunction "2_S2") (pintype "passive"))
    )
    (net (code "42") (name "Net-(S14-2)") (class "Default")
      (node (ref "D14") (pin "A") (pinfunction "A_A") (pintype "passive"))
      (node (ref "S14") (pin "S2") (pinfunction "2_S2") (pintype "passive"))
    )
    (net (code "43") (name "Net-(S15-2)") (class "Default")
      (node (ref "D15") (pin "A") (pinfunction "A_A") (pintype "passive"))
      (node (ref "S15") (pin "S2") (pinfunction "2_S2") (pintype "passive"))
    )
    (net (code "44") (name "Net-(S16-2)") (class "Default")
      (node (ref "D16") (pin "A") (pinfunction "A_A") (pintype "passive"))
      (node (ref "S16") (pin "S2") (pinfunction "2_S2") (pintype "passive"))
    )
    (net (code "45") (name "Net-(S17-2)") (class "Default")
      (node (ref "D17") (pin "A") (pinfunction "A_A") (pintype "passive"))
      (node (ref "S17") (pin "S2") (pinfunction "2_S2") (pintype "passive"))
    )
    (net (code "46") (name "Net-(S18-2)") (class "Default")
      (node (ref "D18") (pin "A") (pinfunction "A_A") (pintype "passive"))
      (node (ref "S18") (pin "S2") (pinfunction "2_S2") (pintype "passive"))
    )
    (net (code "47") (name "Net-(S19-2)") (class "Default")
      (node (ref "D19") (pin "A") (pinfunction "A_A") (pintype "passive"))
      (node (ref "S19") (pin "S2") (pinfunction "2_S2") (pintype "passive"))
    )
    (net (code "48") (name "Net-(S20-2)") (class "Default")
      (node (ref "D20") (pin "A") (pinfunction "A_A") (pintype "passive"))
      (node (ref "S20") (pin "S2") (pinfunction "2_S2") (pintype "passive"))
    )
    (net (code "49") (name "Net-(S21-2)") (class "Default")
      (node (ref "D21") (pin "A") (pinfunction "A_A") (pintype "passive"))
      (node (ref "S21") (pin "S2") (pinfunction "2_S2") (pintype "passive"))
    )
    (net (code "50") (name "Net-(S22-2)") (class "Default")
      (node (ref "D22") (pin "A") (pinfunction "A_A") (pintype "passive"))
      (node (ref "S22") (pin "S2") (pinfunction "2_S2") (pintype "passive"))
    )
    (net (code "51") (name "Net-(S23-2)") (class "Default")
      (node (ref "D23") (pin "A") (pinfunction "A_A") (pintype "passive"))
      (node (ref "S23") (pin "S2") (pinfunction "2_S2") (pintype "passive"))
    )
    (net (code "52") (name "Net-(S24-2)") (class "Default")
      (node (ref "D24") (pin "A") (pinfunction "A_A") (pintype "passive"))
      (node (ref "S24") (pin "S2") (pinfunction "2_S2") (pintype "passive"))
    )
    (net (code "53") (name "Net-(S25-2)") (class "Default")
      (node (ref "D25") (pin "A") (pinfunction "A_A") (pintype "passive"))
      (node (ref "S25") (pin "S2") (pinfunction "2_S2") (pintype "passive"))
    )
    (net (code "54") (name "Net-(S26-2)") (class "Default")
      (node (ref "D26") (pin "A") (pinfunction "A_A") (pintype "passive"))
      (node (ref "S26") (pin "S2") (pinfunction "2_S2") (pintype "passive"))
    )
    (net (code "55") (name "Net-(S27-2)") (class "Default")
      (node (ref "D27") (pin "A") (pinfunction "A_A") (pintype "passive"))
      (node (ref "S27") (pin "S2") (pinfunction "2_S2") (pintype "passive"))
    )
    (net (code "56") (name "Net-(S28-2)") (class "Default")
      (node (ref "D28") (pin "A") (pinfunction "A_A") (pintype "passive"))
      (node (ref "S28") (pin "S2") (pinfunction "2_S2") (pintype "passive"))
    )
    (net (code "57") (name "Net-(S29-2)") (class "Default")
      (node (ref "D29") (pin "A") (pinfunction "A_A") (pintype "passive"))
      (node (ref "S29") (pin "S2") (pinfunction "2_S2") (pintype "passive"))
    )
    (net (code "58") (name "Net-(S30-2)") (class "Default")
      (node (ref "D30") (pin "A") (pinfunction "A_A") (pintype "passive"))
      (node (ref "S30") (pin "S2") (pinfunction "2_S2") (pintype "passive"))
    )
    (net (code "59") (name "Net-(S31-2)") (class "Default")
      (node (ref "D31") (pin "A") (pinfunction "A_A") (pintype "passive"))
      (node (ref "S31") (pin "S2") (pinfunction "2_S2") (pintype "passive"))
    )
    (net (code "60") (name "Net-(S32-2)") (class "Default")
      (node (ref "D32") (pin "A") (pinfunction "A_A") (pintype "passive"))
      (node (ref "S32") (pin "S2") (pinfunction "2_S2") (pintype "passive"))
    )
    (net (code "61") (name "Net-(S33-2)") (class "Default")
      (node (ref "D33") (pin "A") (pinfunction "A_A") (pintype "passive"))
      (node (ref "S33") (pin "S2") (pinfunction "2_S2") (pintype "passive"))
    )
    (net (code "62") (name "Net-(S34-2)") (class "Default")
      (node (ref "D34") (pin "A") (pinfunction "A_A") (pintype "passive"))
      (node (ref "S34") (pin "S2") (pinfunction "2_S2") (pintype "passive"))
    )
    (net (code "63") (name "Net-(S35-2)") (class "Default")
      (node (ref "D35") (pin "A") (pinfunction "A_A") (pintype "passive"))
      (node (ref "S35") (pin "S2") (pinfunction "2_S2") (pintype "passive"))
    )
    (net (code "64") (name "Net-(S36-2)") (class "Default")
      (node (ref "D36") (pin "A") (pinfunction "A_A") (pintype "passive"))
      (node (ref "S36") (pin "S2") (pinfunction "2_S2") (pintype "passive"))
    )
    (net (code "65") (name "Net-(S37-2)") (class "Default")
      (node (ref "D37") (pin "A") (pinfunction "A_A") (pintype "passive"))
      (node (ref "S37") (pin "S2") (pinfunction "2_S2") (pintype "passive"))
    )
    (net (code "66") (name "Net-(S38-2)") (class "Default")
      (node (ref "D38") (pin "A") (pinfunction "A_A") (pintype "passive"))
      (node (ref "S38") (pin "S2") (pinfunction "2_S2") (pintype "passive"))
    )
    (net (code "67") (name "Net-(S39-2)") (class "Default")
      (node (ref "D39") (pin "A") (pinfunction "A_A") (pintype "passive"))
      (node (ref "S39") (pin "S2") (pinfunction "2_S2") (pintype "passive"))
    )
    (net (code "68") (name "Net-(S40-2)") (class "Default")
      (node (ref "D40") (pin "A") (pinfunction "A_A") (pintype "passive"))
      (node (ref "S40") (pin "S2") (pinfunction "2_S2") (pintype "passive"))
    )
    (net (code "69") (name "Net-(S41-2)") (class "Default")
      (node (ref "D41") (pin "A") (pinfunction "A_A") (pintype "passive"))
      (node (ref "S41") (pin "S2") (pinfunction "2_S2") (pintype "passive"))
    )
    (net (code "70") (name "Net-(S42-2)") (class "Default")
      (node (ref "D42") (pin "A") (pinfunction "A_A") (pintype "passive"))
      (node (ref "S42") (pin "S2") (pinfunction "2_S2") (pintype "passive"))
    )
    (net (code "71") (name "Net-(S43-2)") (class "Default")
      (node (ref "D43") (pin "A") (pinfunction "A_A") (pintype "passive"))
      (node (ref "S43") (pin "S2") (pinfunction "2_S2") (pintype "passive"))
    )
    (net (code "72") (name "Net-(S44-2)") (class "Default")
      (node (ref "D44") (pin "A") (pinfunction "A_A") (pintype "passive"))
      (node (ref "S44") (pin "S2") (pinfunction "2_S2") (pintype "passive"))
    )
    (net (code "73") (name "Net-(S45-2)") (class "Default")
      (node (ref "D45") (pin "A") (pinfunction "A_A") (pintype "passive"))
      (node (ref "S45") (pin "S2") (pinfunction "2_S2") (pintype "passive"))
    )
    (net (code "74") (name "Net-(S46-2)") (class "Default")
      (node (ref "D46") (pin "A") (pinfunction "A_A") (pintype "passive"))
      (node (ref "S46") (pin "S2") (pinfunction "2_S2") (pintype "passive"))
    )
    (net (code "75") (name "Net-(S47-2)") (class "Default")
      (node (ref "D47") (pin "A") (pinfunction "A_A") (pintype "passive"))
      (node (ref "S47") (pin "S2") (pinfunction "2_S2") (pintype "passive"))
    )
    (net (code "76") (name "Net-(S48-2)") (class "Default")
      (node (ref "D48") (pin "A") (pinfunction "A_A") (pintype "passive"))
      (node (ref "S48") (pin "S2") (pinfunction "2_S2") (pintype "passive"))
    )
    (net (code "77") (name "Net-(S49-2)") (class "Default")
      (node (ref "D49") (pin "A") (pinfunction "A_A") (pintype "passive"))
      (node (ref "S49") (pin "S2") (pinfunction "2_S2") (pintype "passive"))
    )
    (net (code "78") (name "Net-(S50-2)") (class "Default")
      (node (ref "D50") (pin "A") (pinfunction "A_A") (pintype "passive"))
      (node (ref "S50") (pin "S2") (pinfunction "2_S2") (pintype "passive"))
    )
    (net (code "79") (name "Net-(S51-2)") (class "Default")
      (node (ref "D51") (pin "A") (pinfunction "A_A") (pintype "passive"))
      (node (ref "S51") (pin "S2") (pinfunction "2_S2") (pintype "passive"))
    )
    (net (code "80") (name "Net-(S52-2)") (class "Default")
      (node (ref "D52") (pin "A") (pinfunction "A_A") (pintype "passive"))
      (node (ref "S52") (pin "S2") (pinfunction "2_S2") (pintype "passive"))
    )
    (net (code "81") (name "Net-(S53-2)") (class "Default")
      (node (ref "D53") (pin "A") (pinfunction "A_A") (pintype "passive"))
      (node (ref "S53") (pin "S2") (pinfunction "2_S2") (pintype "passive"))
    )
    (net (code "82") (name "Net-(S54-2)") (class "Default")
      (node (ref "D54") (pin "A") (pinfunction "A_A") (pintype "passive"))
      (node (ref "S54") (pin "S2") (pinfunction "2_S2") (pintype "passive"))
    )
    (net (code "83") (name "Net-(S55-2)") (class "Default")
      (node (ref "D55") (pin "A") (pinfunction "A_A") (pintype "passive"))
      (node (ref "S55") (pin "S2") (pinfunction "2_S2") (pintype "passive"))
    )
    (net (code "84") (name "Net-(S56-2)") (class "Default")
      (node (ref "D56") (pin "A") (pinfunction "A_A") (pintype "passive"))
      (node (ref "S56") (pin "S2") (pinfunction "2_S2") (pintype "passive"))
    )
    (net (code "85") (name "Net-(S57-2)") (class "Default")
      (node (ref "D57") (pin "A") (pinfunction "A_A") (pintype "passive"))
      (node (ref "S57") (pin "S2") (pinfunction "2_S2") (pintype "passive"))
    )
    (net (code "86") (name "Net-(S58-2)") (class "Default")
      (node (ref "D58") (pin "A") (pinfunction "A_A") (pintype "passive"))
      (node (ref "S58") (pin "S2") (pinfunction "2_S2") (pintype "passive"))
    )
    (net (code "87") (name "Net-(S59-2)") (class "Default")
      (node (ref "D59") (pin "A") (pinfunction "A_A") (pintype "passive"))
      (node (ref "S59") (pin "S2") (pinfunction "2_S2") (pintype "passive"))
    )
    (net (code "88") (name "Net-(S60-2)") (class "Default")
      (node (ref "D60") (pin "A") (pinfunction "A_A") (pintype "passive"))
      (node (ref "S60") (pin "S2") (pinfunction "2_S2") (pintype "passive"))
    )
    (net (code "89") (name "Net-(S61-2)") (class "Default")
      (node (ref "D61") (pin "A") (pinfunction "A_A") (pintype "passive"))
      (node (ref "S61") (pin "S2") (pinfunction "2_S2") (pintype "passive"))
    )
    (net (code "90") (name "Net-(S62-2)") (class "Default")
      (node (ref "D62") (pin "A") (pinfunction "A_A") (pintype "passive"))
      (node (ref "S62") (pin "S2") (pinfunction "2_S2") (pintype "passive"))
    )
    (net (code "91") (name "Net-(S63-2)") (class "Default")
      (node (ref "D63") (pin "A") (pinfunction "A_A") (pintype "passive"))
      (node (ref "S63") (pin "S2") (pinfunction "2_S2") (pintype "passive"))
    )
    (net (code "92") (name "Net-(S64-2)") (class "Default")
      (node (ref "D64") (pin "A") (pinfunction "A_A") (pintype "passive"))
      (node (ref "S64") (pin "S2") (pinfunction "2_S2") (pintype "passive"))
    )
    (net (code "93") (name "Net-(S65-2)") (class "Default")
      (node (ref "D65") (pin "A") (pinfunction "A_A") (pintype "passive"))
      (node (ref "S65") (pin "S2") (pinfunction "2_S2") (pintype "passive"))
    )
    (net (code "94") (name "Net-(S66-2)") (class "Default")
      (node (ref "D66") (pin "A") (pinfunction "A_A") (pintype "passive"))
      (node (ref "S66") (pin "S2") (pinfunction "2_S2") (pintype "passive"))
    )
    (net (code "95") (name "Net-(S67-2)") (class "Default")
      (node (ref "D67") (pin "A") (pinfunction "A_A") (pintype "passive"))
      (node (ref "S67") (pin "S2") (pinfunction "2_S2") (pintype "passive"))
    )
    (net (code "96") (name "Net-(S68-2)") (class "Default")
      (node (ref "D68") (pin "A") (pinfunction "A_A") (pintype "passive"))
      (node (ref "S68") (pin "S2") (pinfunction "2_S2") (pintype "passive"))
    )
    (net (code "97") (name "Net-(S69-2)") (class "Default")
      (node (ref "D69") (pin "A") (pinfunction "A_A") (pintype "passive"))
      (node (ref "S69") (pin "S2") (pinfunction "2_S2") (pintype "passive"))
    )
    (net (code "98") (name "Net-(S70-2)") (class "Default")
      (node (ref "D70") (pin "A") (pinfunction "A_A") (pintype "passive"))
      (node (ref "S70") (pin "S2") (pinfunction "2_S2") (pintype "passive"))
    )
    (net (code "99") (name "Net-(S71-2)") (class "Default")
      (node (ref "D71") (pin "A") (pinfunction "A_A") (pintype "passive"))
      (node (ref "S71") (pin "S2") (pinfunction "2_S2") (pintype "passive"))
    )
    (net (code "100") (name "Net-(S72-2)") (class "Default")
      (node (ref "D72") (pin "A") (pinfunction "A_A") (pintype "passive"))
      (node (ref "S72") (pin "S2") (pinfunction "2_S2") (pintype "passive"))
    )
    (net (code "101") (name "Net-(S73-2)") (class "Default")
      (node (ref "D73") (pin "A") (pinfunction "A_A") (pintype "passive"))
      (node (ref "S73") (pin "S2") (pinfunction "2_S2") (pintype "passive"))
    )
    (net (code "102") (name "Net-(S74-2)") (class "Default")
      (node (ref "D74") (pin "A") (pinfunction "A_A") (pintype "passive"))
      (node (ref "S74") (pin "S2") (pinfunction "2_S2") (pintype "passive"))
    )
    (net (code "103") (name "Net-(S75-2)") (class "Default")
      (node (ref "D75") (pin "A") (pinfunction "A_A") (pintype "passive"))
      (node (ref "S75") (pin "S2") (pinfunction "2_S2") (pintype "passive"))
    )
    (net (code "104") (name "Net-(S76-2)") (class "Default")
      (node (ref "D76") (pin "A") (pinfunction "A_A") (pintype "passive"))
      (node (ref "S76") (pin "S2") (pinfunction "2_S2") (pintype "passive"))
    )
    (net (code "105") (name "Net-(S77-2)") (class "Default")
      (node (ref "D77") (pin "A") (pinfunction "A_A") (pintype "passive"))
      (node (ref "S77") (pin "S2") (pinfunction "2_S2") (pintype "passive"))
    )
    (net (code "106") (name "Net-(S78-2)") (class "Default")
      (node (ref "D78") (pin "A") (pinfunction "A_A") (pintype "passive"))
      (node (ref "S78") (pin "S2") (pinfunction "2_S2") (pintype "passive"))
    )
    (net (code "107") (name "Net-(S79-2)") (class "Default")
      (node (ref "D79") (pin "A") (pinfunction "A_A") (pintype "passive"))
      (node (ref "S79") (pin "S2") (pinfunction "2_S2") (pintype "passive"))
    )
    (net (code "108") (name "Net-(U$1-A5CC1)") (class "Default")
      (node (ref "R3") (pin "1") (pinfunction "1_1") (pintype "passive"))
      (node (ref "R7") (pin "1") (pinfunction "1_1") (pintype "passive"))
      (node (ref "U$1") (pin "A5") (pinfunction "A5CC1_A5") (pintype "bidirectional"))
    )
    (net (code "109") (name "Net-(U$1-A6DP1)") (class "Default")
      (node (ref "R2") (pin "1") (pinfunction "1_1") (pintype "passive"))
      (node (ref "U$1") (pin "A6") (pinfunction "A6DP1_A6") (pintype "bidirectional"))
      (node (ref "U$1") (pin "B6") (pinfunction "B6DP2_B6") (pintype "bidirectional"))
    )
    (net (code "110") (name "Net-(U$1-A7DN1)") (class "Default")
      (node (ref "R1") (pin "1") (pinfunction "1_1") (pintype "passive"))
      (node (ref "U$1") (pin "A7") (pinfunction "A7DN1_A7") (pintype "bidirectional"))
      (node (ref "U$1") (pin "B7") (pinfunction "B7DN2_B7") (pintype "bidirectional"))
    )
    (net (code "111") (name "Net-(U$1-B5CC2)") (class "Default")
      (node (ref "R4") (pin "1") (pinfunction "1_1") (pintype "passive"))
      (node (ref "R8") (pin "1") (pinfunction "1_1") (pintype "passive"))
      (node (ref "U$1") (pin "B5") (pinfunction "B5CC2_B5") (pintype "bidirectional"))
    )
    (net (code "112") (name "R1") (class "Default")
      (node (ref "ATMEGA32U4-AU") (pin "41") (pinfunction "PF0_41") (pintype "bidirectional"))
      (node (ref "S1") (pin "S1") (pinfunction "1_S1") (pintype "passive"))
      (node (ref "S10") (pin "S1") (pinfunction "1_S1") (pintype "passive"))
      (node (ref "S11") (pin "S1") (pinfunction "1_S1") (pintype "passive"))
      (node (ref "S12") (pin "S1") (pinfunction "1_S1") (pintype "passive"))
      (node (ref "S13") (pin "S1") (pinfunction "1_S1") (pintype "passive"))
      (node (ref "S14") (pin "S1") (pinfunction "1_S1") (pintype "passive"))
      (node (ref "S15") (pin "S1") (pinfunction "1_S1") (pintype "passive"))
      (node (ref "S16") (pin "S1") (pinfunction "1_S1") (pintype "passive"))
      (node (ref "S17") (pin "S1") (pinfunction "1_S1") (pintype "passive"))
      (node (ref "S2") (pin "S1") (pinfunction "1_S1") (pintype "passive"))
      (node (ref "S3") (pin "S1") (pinfunction "1_S1") (pintype "passive"))
      (node (ref "S4") (pin "S1") (pinfunction "1_S1") (pintype "passive"))
      (node (ref "S5") (pin "S1") (pinfunction "1_S1") (pintype "passive"))
      (node (ref "S6") (pin "S1") (pinfunction "1_S1") (pintype "passive"))
      (node (ref "S7") (pin "S1") (pinfunction "1_S1") (pintype "passive"))
      (node (ref "S8") (pin "S1") (pinfunction "1_S1") (pintype "passive"))
      (node (ref "S9") (pin "S1") (pinfunction "1_S1") (pintype "passive"))
    )
    (net (code "113") (name "R2") (class "Default")
      (node (ref "ATMEGA32U4-AU") (pin "40") (pinfunction "PF1_40") (pintype "bidirectional"))
      (node (ref "S18") (pin "S1") (pinfunction "1_S1") (pintype "passive"))
      (node (ref "S19") (pin "S1") (pinfunction "1_S1") (pintype "passive"))
      (node (ref "S20") (pin "S1") (pinfunction "1_S1") (pintype "passive"))
      (node (ref "S21") (pin "S1") (pinfunction "1_S1") (pintype "passive"))
      (node (ref "S22") (pin "S1") (pinfunction "1_S1") (pintype "passive"))
      (node (ref "S23") (pin "S1") (pinfunction "1_S1") (pintype "passive"))
      (node (ref "S24") (pin "S1") (pinfunction "1_S1") (pintype "passive"))
      (node (ref "S25") (pin "S1") (pinfunction "1_S1") (pintype "passive"))
      (node (ref "S26") (pin "S1") (pinfunction "1_S1") (pintype "passive"))
      (node (ref "S27") (pin "S1") (pinfunction "1_S1") (pintype "passive"))
      (node (ref "S28") (pin "S1") (pinfunction "1_S1") (pintype "passive"))
      (node (ref "S29") (pin "S1") (pinfunction "1_S1") (pintype "passive"))
      (node (ref "S30") (pin "S1") (pinfunction "1_S1") (pintype "passive"))
      (node (ref "S31") (pin "S1") (pinfunction "1_S1") (pintype "passive"))
      (node (ref "S32") (pin "S1") (pinfunction "1_S1") (pintype "passive"))
      (node (ref "S33") (pin "S1") (pinfunction "1_S1") (pintype "passive"))
      (node (ref "S34") (pin "S1") (pinfunction "1_S1") (pintype "passive"))
    )
    (net (code "114") (name "R3") (class "Default")
      (node (ref "ATMEGA32U4-AU") (pin "39") (pinfunction "PF4_39") (pintype "bidirectional"))
      (node (ref "S35") (pin "S1") (pinfunction "1_S1") (pintype "passive"))
      (node (ref "S36") (pin "S1") (pinfunction "1_S1") (pintype "passive"))
      (node (ref "S37") (pin "S1") (pinfunction "1_S1") (pintype "passive"))
      (node (ref "S38") (pin "S1") (pinfunction "1_S1") (pintype "passive"))
      (node (ref "S39") (pin "S1") (pinfunction "1_S1") (pintype "passive"))
      (node (ref "S40") (pin "S1") (pinfunction "1_S1") (pintype "passive"))
      (node (ref "S41") (pin "S1") (pinfunction "1_S1") (pintype "passive"))
      (node (ref "S42") (pin "S1") (pinfunction "1_S1") (pintype "passive"))
      (node (ref "S43") (pin "S1") (pinfunction "1_S1") (pintype "passive"))
      (node (ref "S44") (pin "S1") (pinfunction "1_S1") (pintype "passive"))
      (node (ref "S45") (pin "S1") (pinfunction "1_S1") (pintype "passive"))
      (node (ref "S46") (pin "S1") (pinfunction "1_S1") (pintype "passive"))
      (node (ref "S47") (pin "S1") (pinfunction "1_S1") (pintype "passive"))
      (node (ref "S48") (pin "S1") (pinfunction "1_S1") (pintype "passive"))
      (node (ref "S49") (pin "S1") (pinfunction "1_S1") (pintype "passive"))
      (node (ref "S50") (pin "S1") (pinfunction "1_S1") (pintype "passive"))
    )
    (net (code "115") (name "R4") (class "Default")
      (node (ref "ATMEGA32U4-AU") (pin "38") (pinfunction "PF5_38") (pintype "bidirectional"))
      (node (ref "S51") (pin "S1") (pinfunction "1_S1") (pintype "passive"))
      (node (ref "S52") (pin "S1") (pinfunction "1_S1") (pintype "passive"))
      (node (ref "S53") (pin "S1") (pinfunction "1_S1") (pintype "passive"))
      (node (ref "S54") (pin "S1") (pinfunction "1_S1") (pintype "passive"))
      (node (ref "S55") (pin "S1") (pinfunction "1_S1") (pintype "passive"))
      (node (ref "S56") (pin "S1") (pinfunction "1_S1") (pintype "passive"))
      (node (ref "S57") (pin "S1") (pinfunction "1_S1") (pintype "passive"))
      (node (ref "S58") (pin "S1") (pinfunction "1_S1") (pintype "passive"))
      (node (ref "S59") (pin "S1") (pinfunction "1_S1") (pintype "passive"))
      (node (ref "S60") (pin "S1") (pinfunction "1_S1") (pintype "passive"))
      (node (ref "S61") (pin "S1") (pinfunction "1_S1") (pintype "passive"))
      (node (ref "S62") (pin "S1") (pinfunction "1_S1") (pintype "passive"))
      (node (ref "S63") (pin "S1") (pinfunction "1_S1") (pintype "passive"))
      (node (ref "S64") (pin "S1") (pinfunction "1_S1") (pintype "passive"))
      (node (ref "S65") (pin "S1") (pinfunction "1_S1") (pintype "passive"))
      (node (ref "S66") (pin "S1") (pinfunction "1_S1") (pintype "passive"))
    )
    (net (code "116") (name "R5") (class "Default")
      (node (ref "ATMEGA32U4-AU") (pin "37") (pinfunction "PF6_37") (pintype "bidirectional"))
      (node (ref "S67") (pin "S1") (pinfunction "1_S1") (pintype "passive"))
      (node (ref "S68") (pin "S1") (pinfunction "1_S1") (pintype "passive"))
      (node (ref "S69") (pin "S1") (pinfunction "1_S1") (pintype "passive"))
      (node (ref "S70") (pin "S1") (pinfunction "1_S1") (pintype "passive"))
      (node (ref "S71") (pin "S1") (pinfunction "1_S1") (pintype "passive"))
      (node (ref "S72") (pin "S1") (pinfunction "1_S1") (pintype "passive"))
      (node (ref "S73") (pin "S1") (pinfunction "1_S1") (pintype "passive"))
      (node (ref "S74") (pin "S1") (pinfunction "1_S1") (pintype "passive"))
      (node (ref "S75") (pin "S1") (pinfunction "1_S1") (pintype "passive"))
      (node (ref "S76") (pin "S1") (pinfunction "1_S1") (pintype "passive"))
      (node (ref "S77") (pin "S1") (pinfunction "1_S1") (pintype "passive"))
      (node (ref "S78") (pin "S1") (pinfunction "1_S1") (pintype "passive"))
      (node (ref "S79") (pin "S1") (pinfunction "1_S1") (pintype "passive"))
    )
    (net (code "117") (name "unconnected-(ATMEGA32U4-AU-AREF-Pad42)") (class "Default")
      (node (ref "ATMEGA32U4-AU") (pin "42") (pinfunction "AREF_42") (pintype "input"))
    )
    (net (code "118") (name "unconnected-(ATMEGA32U4-AU-PD6-Pad26)") (class "Default")
      (node (ref "ATMEGA32U4-AU") (pin "26") (pinfunction "PD6_26") (pintype "bidirectional"))
    )
    (net (code "119") (name "unconnected-(ATMEGA32U4-AU-PF7-Pad36)") (class "Default")
      (node (ref "ATMEGA32U4-AU") (pin "36") (pinfunction "PF7_36") (pintype "bidirectional"))
    )
    (net (code "120") (name "unconnected-(S1-C-PadK)") (class "Default")
      (node (ref "S1") (pin "K") (pinfunction "C_K") (pintype "passive"))
    )
    (net (code "121") (name "unconnected-(S1-PadA)") (class "Default")
      (node (ref "S1") (pin "A") (pinfunction "A_A") (pintype "passive"))
    )
    (net (code "122") (name "unconnected-(S2-C-PadK)") (class "Default")
      (node (ref "S2") (pin "K") (pinfunction "C_K") (pintype "passive"))
    )
    (net (code "123") (name "unconnected-(S2-PadA)") (class "Default")
      (node (ref "S2") (pin "A") (pinfunction "A_A") (pintype "passive"))
    )
    (net (code "124") (name "unconnected-(S3-C-PadK)") (class "Default")
      (node (ref "S3") (pin "K") (pinfunction "C_K") (pintype "passive"))
    )
    (net (code "125") (name "unconnected-(S3-PadA)") (class "Default")
      (node (ref "S3") (pin "A") (pinfunction "A_A") (pintype "passive"))
    )
    (net (code "126") (name "unconnected-(S4-C-PadK)") (class "Default")
      (node (ref "S4") (pin "K") (pinfunction "C_K") (pintype "passive"))
    )
    (net (code "127") (name "unconnected-(S4-PadA)") (class "Default")
      (node (ref "S4") (pin "A") (pinfunction "A_A") (pintype "passive"))
    )
    (net (code "128") (name "unconnected-(S5-C-PadK)") (class "Default")
      (node (ref "S5") (pin "K") (pinfunction "C_K") (pintype "passive"))
    )
    (net (code "129") (name "unconnected-(S5-PadA)") (class "Default")
      (node (ref "S5") (pin "A") (pinfunction "A_A") (pintype "passive"))
    )
    (net (code "130") (name "unconnected-(S6-C-PadK)") (class "Default")
      (node (ref "S6") (pin "K") (pinfunction "C_K") (pintype "passive"))
    )
    (net (code "131") (name "unconnected-(S6-PadA)") (class "Default")
      (node (ref "S6") (pin "A") (pinfunction "A_A") (pintype "passive"))
    )
    (net (code "132") (name "unconnected-(S7-C-PadK)") (class "Default")
      (node (ref "S7") (pin "K") (pinfunction "C_K") (pintype "passive"))
    )
    (net (code "133") (name "unconnected-(S7-PadA)") (class "Default")
      (node (ref "S7") (pin "A") (pinfunction "A_A") (pintype "passive"))
    )
    (net (code "134") (name "unconnected-(S8-C-PadK)") (class "Default")
      (node (ref "S8") (pin "K") (pinfunction "C_K") (pintype "passive"))
    )
    (net (code "135") (name "unconnected-(S8-PadA)") (class "Default")
      (node (ref "S8") (pin "A") (pinfunction "A_A") (pintype "passive"))
    )
    (net (code "136") (name "unconnected-(S9-C-PadK)") (class "Default")
      (node (ref "S9") (pin "K") (pinfunction "C_K") (pintype "passive"))
    )
    (net (code "137") (name "unconnected-(S9-PadA)") (class "Default")
      (node (ref "S9") (pin "A") (pinfunction "A_A") (pintype "passive"))
    )
    (net (code "138") (name "unconnected-(S10-C-PadK)") (class "Default")
      (node (ref "S10") (pin "K") (pinfunction "C_K") (pintype "passive"))
    )
    (net (code "139") (name "unconnected-(S10-PadA)") (class "Default")
      (node (ref "S10") (pin "A") (pinfunction "A_A") (pintype "passive"))
    )
    (net (code "140") (name "unconnected-(S11-C-PadK)") (class "Default")
      (node (ref "S11") (pin "K") (pinfunction "C_K") (pintype "passive"))
    )
    (net (code "141") (name "unconnected-(S11-PadA)") (class "Default")
      (node (ref "S11") (pin "A") (pinfunction "A_A") (pintype "passive"))
    )
    (net (code "142") (name "unconnected-(S12-C-PadK)") (class "Default")
      (node (ref "S12") (pin "K") (pinfunction "C_K") (pintype "passive"))
    )
    (net (code "143") (name "unconnected-(S12-PadA)") (class "Default")
      (node (ref "S12") (pin "A") (pinfunction "A_A") (pintype "passive"))
    )
    (net (code "144") (name "unconnected-(S13-C-PadK)") (class "Default")
      (node (ref "S13") (pin "K") (pinfunction "C_K") (pintype "passive"))
    )
    (net (code "145") (name "unconnected-(S13-PadA)") (class "Default")
      (node (ref "S13") (pin "A") (pinfunction "A_A") (pintype "passive"))
    )
    (net (code "146") (name "unconnected-(S14-C-PadK)") (class "Default")
      (node (ref "S14") (pin "K") (pinfunction "C_K") (pintype "passive"))
    )
    (net (code "147") (name "unconnected-(S14-PadA)") (class "Default")
      (node (ref "S14") (pin "A") (pinfunction "A_A") (pintype "passive"))
    )
    (net (code "148") (name "unconnected-(S15-C-PadK)") (class "Default")
      (node (ref "S15") (pin "K") (pinfunction "C_K") (pintype "passive"))
    )
    (net (code "149") (name "unconnected-(S15-PadA)") (class "Default")
      (node (ref "S15") (pin "A") (pinfunction "A_A") (pintype "passive"))
    )
    (net (code "150") (name "unconnected-(S16-C-PadK)") (class "Default")
      (node (ref "S16") (pin "K") (pinfunction "C_K") (pintype "passive"))
    )
    (net (code "151") (name "unconnected-(S16-PadA)") (class "Default")
      (node (ref "S16") (pin "A") (pinfunction "A_A") (pintype "passive"))
    )
    (net (code "152") (name "unconnected-(S17-C-PadK)") (class "Default")
      (node (ref "S17") (pin "K") (pinfunction "C_K") (pintype "passive"))
    )
    (net (code "153") (name "unconnected-(S17-PadA)") (class "Default")
      (node (ref "S17") (pin "A") (pinfunction "A_A") (pintype "passive"))
    )
    (net (code "154") (name "unconnected-(S18-C-PadK)") (class "Default")
      (node (ref "S18") (pin "K") (pinfunction "C_K") (pintype "passive"))
    )
    (net (code "155") (name "unconnected-(S18-PadA)") (class "Default")
      (node (ref "S18") (pin "A") (pinfunction "A_A") (pintype "passive"))
    )
    (net (code "156") (name "unconnected-(S19-C-PadK)") (class "Default")
      (node (ref "S19") (pin "K") (pinfunction "C_K") (pintype "passive"))
    )
    (net (code "157") (name "unconnected-(S19-PadA)") (class "Default")
      (node (ref "S19") (pin "A") (pinfunction "A_A") (pintype "passive"))
    )
    (net (code "158") (name "unconnected-(S20-C-PadK)") (class "Default")
      (node (ref "S20") (pin "K") (pinfunction "C_K") (pintype "passive"))
    )
    (net (code "159") (name "unconnected-(S20-PadA)") (class "Default")
      (node (ref "S20") (pin "A") (pinfunction "A_A") (pintype "passive"))
    )
    (net (code "160") (name "unconnected-(S21-C-PadK)") (class "Default")
      (node (ref "S21") (pin "K") (pinfunction "C_K") (pintype "passive"))
    )
    (net (code "161") (name "unconnected-(S21-PadA)") (class "Default")
      (node (ref "S21") (pin "A") (pinfunction "A_A") (pintype "passive"))
    )
    (net (code "162") (name "unconnected-(S22-C-PadK)") (class "Default")
      (node (ref "S22") (pin "K") (pinfunction "C_K") (pintype "passive"))
    )
    (net (code "163") (name "unconnected-(S22-PadA)") (class "Default")
      (node (ref "S22") (pin "A") (pinfunction "A_A") (pintype "passive"))
    )
    (net (code "164") (name "unconnected-(S23-C-PadK)") (class "Default")
      (node (ref "S23") (pin "K") (pinfunction "C_K") (pintype "passive"))
    )
    (net (code "165") (name "unconnected-(S23-PadA)") (class "Default")
      (node (ref "S23") (pin "A") (pinfunction "A_A") (pintype "passive"))
    )
    (net (code "166") (name "unconnected-(S24-C-PadK)") (class "Default")
      (node (ref "S24") (pin "K") (pinfunction "C_K") (pintype "passive"))
    )
    (net (code "167") (name "unconnected-(S24-PadA)") (class "Default")
      (node (ref "S24") (pin "A") (pinfunction "A_A") (pintype "passive"))
    )
    (net (code "168") (name "unconnected-(S25-C-PadK)") (class "Default")
      (node (ref "S25") (pin "K") (pinfunction "C_K") (pintype "passive"))
    )
    (net (code "169") (name "unconnected-(S25-PadA)") (class "Default")
      (node (ref "S25") (pin "A") (pinfunction "A_A") (pintype "passive"))
    )
    (net (code "170") (name "unconnected-(S26-C-PadK)") (class "Default")
      (node (ref "S26") (pin "K") (pinfunction "C_K") (pintype "passive"))
    )
    (net (code "171") (name "unconnected-(S26-PadA)") (class "Default")
      (node (ref "S26") (pin "A") (pinfunction "A_A") (pintype "passive"))
    )
    (net (code "172") (name "unconnected-(S27-C-PadK)") (class "Default")
      (node (ref "S27") (pin "K") (pinfunction "C_K") (pintype "passive"))
    )
    (net (code "173") (name "unconnected-(S27-PadA)") (class "Default")
      (node (ref "S27") (pin "A") (pinfunction "A_A") (pintype "passive"))
    )
    (net (code "174") (name "unconnected-(S28-C-PadK)") (class "Default")
      (node (ref "S28") (pin "K") (pinfunction "C_K") (pintype "passive"))
    )
    (net (code "175") (name "unconnected-(S28-PadA)") (class "Default")
      (node (ref "S28") (pin "A") (pinfunction "A_A") (pintype "passive"))
    )
    (net (code "176") (name "unconnected-(S29-C-PadK)") (class "Default")
      (node (ref "S29") (pin "K") (pinfunction "C_K") (pintype "passive"))
    )
    (net (code "177") (name "unconnected-(S29-PadA)") (class "Default")
      (node (ref "S29") (pin "A") (pinfunction "A_A") (pintype "passive"))
    )
    (net (code "178") (name "unconnected-(S30-C-PadK)") (class "Default")
      (node (ref "S30") (pin "K") (pinfunction "C_K") (pintype "passive"))
    )
    (net (code "179") (name "unconnected-(S30-PadA)") (class "Default")
      (node (ref "S30") (pin "A") (pinfunction "A_A") (pintype "passive"))
    )
    (net (code "180") (name "unconnected-(S31-C-PadK)") (class "Default")
      (node (ref "S31") (pin "K") (pinfunction "C_K") (pintype "passive"))
    )
    (net (code "181") (name "unconnected-(S31-PadA)") (class "Default")
      (node (ref "S31") (pin "A") (pinfunction "A_A") (pintype "passive"))
    )
    (net (code "182") (name "unconnected-(S32-C-PadK)") (class "Default")
      (node (ref "S32") (pin "K") (pinfunction "C_K") (pintype "passive"))
    )
    (net (code "183") (name "unconnected-(S32-PadA)") (class "Default")
      (node (ref "S32") (pin "A") (pinfunction "A_A") (pintype "passive"))
    )
    (net (code "184") (name "unconnected-(S33-C-PadK)") (class "Default")
      (node (ref "S33") (pin "K") (pinfunction "C_K") (pintype "passive"))
    )
    (net (code "185") (name "unconnected-(S33-PadA)") (class "Default")
      (node (ref "S33") (pin "A") (pinfunction "A_A") (pintype "passive"))
    )
    (net (code "186") (name "unconnected-(S34-C-PadK)") (class "Default")
      (node (ref "S34") (pin "K") (pinfunction "C_K") (pintype "passive"))
    )
    (net (code "187") (name "unconnected-(S34-PadA)") (class "Default")
      (node (ref "S34") (pin "A") (pinfunction "A_A") (pintype "passive"))
    )
    (net (code "188") (name "unconnected-(S35-C-PadK)") (class "Default")
      (node (ref "S35") (pin "K") (pinfunction "C_K") (pintype "passive"))
    )
    (net (code "189") (name "unconnected-(S35-PadA)") (class "Default")
      (node (ref "S35") (pin "A") (pinfunction "A_A") (pintype "passive"))
    )
    (net (code "190") (name "unconnected-(S36-C-PadK)") (class "Default")
      (node (ref "S36") (pin "K") (pinfunction "C_K") (pintype "passive"))
    )
    (net (code "191") (name "unconnected-(S36-PadA)") (class "Default")
      (node (ref "S36") (pin "A") (pinfunction "A_A") (pintype "passive"))
    )
    (net (code "192") (name "unconnected-(S37-C-PadK)") (class "Default")
      (node (ref "S37") (pin "K") (pinfunction "C_K") (pintype "passive"))
    )
    (net (code "193") (name "unconnected-(S37-PadA)") (class "Default")
      (node (ref "S37") (pin "A") (pinfunction "A_A") (pintype "passive"))
    )
    (net (code "194") (name "unconnected-(S38-C-PadK)") (class "Default")
      (node (ref "S38") (pin "K") (pinfunction "C_K") (pintype "passive"))
    )
    (net (code "195") (name "unconnected-(S38-PadA)") (class "Default")
      (node (ref "S38") (pin "A") (pinfunction "A_A") (pintype "passive"))
    )
    (net (code "196") (name "unconnected-(S39-C-PadK)") (class "Default")
      (node (ref "S39") (pin "K") (pinfunction "C_K") (pintype "passive"))
    )
    (net (code "197") (name "unconnected-(S39-PadA)") (class "Default")
      (node (ref "S39") (pin "A") (pinfunction "A_A") (pintype "passive"))
    )
    (net (code "198") (name "unconnected-(S40-C-PadK)") (class "Default")
      (node (ref "S40") (pin "K") (pinfunction "C_K") (pintype "passive"))
    )
    (net (code "199") (name "unconnected-(S40-PadA)") (class "Default")
      (node (ref "S40") (pin "A") (pinfunction "A_A") (pintype "passive"))
    )
    (net (code "200") (name "unconnected-(S41-C-PadK)") (class "Default")
      (node (ref "S41") (pin "K") (pinfunction "C_K") (pintype "passive"))
    )
    (net (code "201") (name "unconnected-(S41-PadA)") (class "Default")
      (node (ref "S41") (pin "A") (pinfunction "A_A") (pintype "passive"))
    )
    (net (code "202") (name "unconnected-(S42-C-PadK)") (class "Default")
      (node (ref "S42") (pin "K") (pinfunction "C_K") (pintype "passive"))
    )
    (net (code "203") (name "unconnected-(S42-PadA)") (class "Default")
      (node (ref "S42") (pin "A") (pinfunction "A_A") (pintype "passive"))
    )
    (net (code "204") (name "unconnected-(S43-C-PadK)") (class "Default")
      (node (ref "S43") (pin "K") (pinfunction "C_K") (pintype "passive"))
    )
    (net (code "205") (name "unconnected-(S43-PadA)") (class "Default")
      (node (ref "S43") (pin "A") (pinfunction "A_A") (pintype "passive"))
    )
    (net (code "206") (name "unconnected-(S44-C-PadK)") (class "Default")
      (node (ref "S44") (pin "K") (pinfunction "C_K") (pintype "passive"))
    )
    (net (code "207") (name "unconnected-(S44-PadA)") (class "Default")
      (node (ref "S44") (pin "A") (pinfunction "A_A") (pintype "passive"))
    )
    (net (code "208") (name "unconnected-(S45-C-PadK)") (class "Default")
      (node (ref "S45") (pin "K") (pinfunction "C_K") (pintype "passive"))
    )
    (net (code "209") (name "unconnected-(S45-PadA)") (class "Default")
      (node (ref "S45") (pin "A") (pinfunction "A_A") (pintype "passive"))
    )
    (net (code "210") (name "unconnected-(S46-C-PadK)") (class "Default")
      (node (ref "S46") (pin "K") (pinfunction "C_K") (pintype "passive"))
    )
    (net (code "211") (name "unconnected-(S46-PadA)") (class "Default")
      (node (ref "S46") (pin "A") (pinfunction "A_A") (pintype "passive"))
    )
    (net (code "212") (name "unconnected-(S47-C-PadK)") (class "Default")
      (node (ref "S47") (pin "K") (pinfunction "C_K") (pintype "passive"))
    )
    (net (code "213") (name "unconnected-(S47-PadA)") (class "Default")
      (node (ref "S47") (pin "A") (pinfunction "A_A") (pintype "passive"))
    )
    (net (code "214") (name "unconnected-(S48-C-PadK)") (class "Default")
      (node (ref "S48") (pin "K") (pinfunction "C_K") (pintype "passive"))
    )
    (net (code "215") (name "unconnected-(S48-PadA)") (class "Default")
      (node (ref "S48") (pin "A") (pinfunction "A_A") (pintype "passive"))
    )
    (net (code "216") (name "unconnected-(S49-C-PadK)") (class "Default")
      (node (ref "S49") (pin "K") (pinfunction "C_K") (pintype "passive"))
    )
    (net (code "217") (name "unconnected-(S49-PadA)") (class "Default")
      (node (ref "S49") (pin "A") (pinfunction "A_A") (pintype "passive"))
    )
    (net (code "218") (name "unconnected-(S50-C-PadK)") (class "Default")
      (node (ref "S50") (pin "K") (pinfunction "C_K") (pintype "passive"))
    )
    (net (code "219") (name "unconnected-(S50-PadA)") (class "Default")
      (node (ref "S50") (pin "A") (pinfunction "A_A") (pintype "passive"))
    )
    (net (code "220") (name "unconnected-(S51-C-PadK)") (class "Default")
      (node (ref "S51") (pin "K") (pinfunction "C_K") (pintype "passive"))
    )
    (net (code "221") (name "unconnected-(S51-PadA)") (class "Default")
      (node (ref "S51") (pin "A") (pinfunction "A_A") (pintype "passive"))
    )
    (net (code "222") (name "unconnected-(S52-C-PadK)") (class "Default")
      (node (ref "S52") (pin "K") (pinfunction "C_K") (pintype "passive"))
    )
    (net (code "223") (name "unconnected-(S52-PadA)") (class "Default")
      (node (ref "S52") (pin "A") (pinfunction "A_A") (pintype "passive"))
    )
    (net (code "224") (name "unconnected-(S53-C-PadK)") (class "Default")
      (node (ref "S53") (pin "K") (pinfunction "C_K") (pintype "passive"))
    )
    (net (code "225") (name "unconnected-(S53-PadA)") (class "Default")
      (node (ref "S53") (pin "A") (pinfunction "A_A") (pintype "passive"))
    )
    (net (code "226") (name "unconnected-(S54-C-PadK)") (class "Default")
      (node (ref "S54") (pin "K") (pinfunction "C_K") (pintype "passive"))
    )
    (net (code "227") (name "unconnected-(S54-PadA)") (class "Default")
      (node (ref "S54") (pin "A") (pinfunction "A_A") (pintype "passive"))
    )
    (net (code "228") (name "unconnected-(S55-C-PadK)") (class "Default")
      (node (ref "S55") (pin "K") (pinfunction "C_K") (pintype "passive"))
    )
    (net (code "229") (name "unconnected-(S55-PadA)") (class "Default")
      (node (ref "S55") (pin "A") (pinfunction "A_A") (pintype "passive"))
    )
    (net (code "230") (name "unconnected-(S56-C-PadK)") (class "Default")
      (node (ref "S56") (pin "K") (pinfunction "C_K") (pintype "passive"))
    )
    (net (code "231") (name "unconnected-(S56-PadA)") (class "Default")
      (node (ref "S56") (pin "A") (pinfunction "A_A") (pintype "passive"))
    )
    (net (code "232") (name "unconnected-(S57-C-PadK)") (class "Default")
      (node (ref "S57") (pin "K") (pinfunction "C_K") (pintype "passive"))
    )
    (net (code "233") (name "unconnected-(S57-PadA)") (class "Default")
      (node (ref "S57") (pin "A") (pinfunction "A_A") (pintype "passive"))
    )
    (net (code "234") (name "unconnected-(S58-C-PadK)") (class "Default")
      (node (ref "S58") (pin "K") (pinfunction "C_K") (pintype "passive"))
    )
    (net (code "235") (name "unconnected-(S58-PadA)") (class "Default")
      (node (ref "S58") (pin "A") (pinfunction "A_A") (pintype "passive"))
    )
    (net (code "236") (name "unconnected-(S59-C-PadK)") (class "Default")
      (node (ref "S59") (pin "K") (pinfunction "C_K") (pintype "passive"))
    )
    (net (code "237") (name "unconnected-(S59-PadA)") (class "Default")
      (node (ref "S59") (pin "A") (pinfunction "A_A") (pintype "passive"))
    )
    (net (code "238") (name "unconnected-(S60-C-PadK)") (class "Default")
      (node (ref "S60") (pin "K") (pinfunction "C_K") (pintype "passive"))
    )
    (net (code "239") (name "unconnected-(S60-PadA)") (class "Default")
      (node (ref "S60") (pin "A") (pinfunction "A_A") (pintype "passive"))
    )
    (net (code "240") (name "unconnected-(S61-C-PadK)") (class "Default")
      (node (ref "S61") (pin "K") (pinfunction "C_K") (pintype "passive"))
    )
    (net (code "241") (name "unconnected-(S61-PadA)") (class "Default")
      (node (ref "S61") (pin "A") (pinfunction "A_A") (pintype "passive"))
    )
    (net (code "242") (name "unconnected-(S62-C-PadK)") (class "Default")
      (node (ref "S62") (pin "K") (pinfunction "C_K") (pintype "passive"))
    )
    (net (code "243") (name "unconnected-(S62-PadA)") (class "Default")
      (node (ref "S62") (pin "A") (pinfunction "A_A") (pintype "passive"))
    )
    (net (code "244") (name "unconnected-(S63-C-PadK)") (class "Default")
      (node (ref "S63") (pin "K") (pinfunction "C_K") (pintype "passive"))
    )
    (net (code "245") (name "unconnected-(S63-PadA)") (class "Default")
      (node (ref "S63") (pin "A") (pinfunction "A_A") (pintype "passive"))
    )
    (net (code "246") (name "unconnected-(S64-C-PadK)") (class "Default")
      (node (ref "S64") (pin "K") (pinfunction "C_K") (pintype "passive"))
    )
    (net (code "247") (name "unconnected-(S64-PadA)") (class "Default")
      (node (ref "S64") (pin "A") (pinfunction "A_A") (pintype "passive"))
    )
    (net (code "248") (name "unconnected-(S65-C-PadK)") (class "Default")
      (node (ref "S65") (pin "K") (pinfunction "C_K") (pintype "passive"))
    )
    (net (code "249") (name "unconnected-(S65-PadA)") (class "Default")
      (node (ref "S65") (pin "A") (pinfunction "A_A") (pintype "passive"))
    )
    (net (code "250") (name "unconnected-(S66-C-PadK)") (class "Default")
      (node (ref "S66") (pin "K") (pinfunction "C_K") (pintype "passive"))
    )
    (net (code "251") (name "unconnected-(S66-PadA)") (class "Default")
      (node (ref "S66") (pin "A") (pinfunction "A_A") (pintype "passive"))
    )
    (net (code "252") (name "unconnected-(S67-C-PadK)") (class "Default")
      (node (ref "S67") (pin "K") (pinfunction "C_K") (pintype "passive"))
    )
    (net (code "253") (name "unconnected-(S67-PadA)") (class "Default")
      (node (ref "S67") (pin "A") (pinfunction "A_A") (pintype "passive"))
    )
    (net (code "254") (name "unconnected-(S68-C-PadK)") (class "Default")
      (node (ref "S68") (pin "K") (pinfunction "C_K") (pintype "passive"))
    )
    (net (code "255") (name "unconnected-(S68-PadA)") (class "Default")
      (node (ref "S68") (pin "A") (pinfunction "A_A") (pintype "passive"))
    )
    (net (code "256") (name "unconnected-(S69-C-PadK)") (class "Default")
      (node (ref "S69") (pin "K") (pinfunction "C_K") (pintype "passive"))
    )
    (net (code "257") (name "unconnected-(S69-PadA)") (class "Default")
      (node (ref "S69") (pin "A") (pinfunction "A_A") (pintype "passive"))
    )
    (net (code "258") (name "unconnected-(S70-C-PadK)") (class "Default")
      (node (ref "S70") (pin "K") (pinfunction "C_K") (pintype "passive"))
    )
    (net (code "259") (name "unconnected-(S70-PadA)") (class "Default")
      (node (ref "S70") (pin "A") (pinfunction "A_A") (pintype "passive"))
    )
    (net (code "260") (name "unconnected-(S71-C-PadK)") (class "Default")
      (node (ref "S71") (pin "K") (pinfunction "C_K") (pintype "passive"))
    )
    (net (code "261") (name "unconnected-(S71-PadA)") (class "Default")
      (node (ref "S71") (pin "A") (pinfunction "A_A") (pintype "passive"))
    )
    (net (code "262") (name "unconnected-(S72-C-PadK)") (class "Default")
      (node (ref "S72") (pin "K") (pinfunction "C_K") (pintype "passive"))
    )
    (net (code "263") (name "unconnected-(S72-PadA)") (class "Default")
      (node (ref "S72") (pin "A") (pinfunction "A_A") (pintype "passive"))
    )
    (net (code "264") (name "unconnected-(S73-C-PadK)") (class "Default")
      (node (ref "S73") (pin "K") (pinfunction "C_K") (pintype "passive"))
    )
    (net (code "265") (name "unconnected-(S73-PadA)") (class "Default")
      (node (ref "S73") (pin "A") (pinfunction "A_A") (pintype "passive"))
    )
    (net (code "266") (name "unconnected-(S74-C-PadK)") (class "Default")
      (node (ref "S74") (pin "K") (pinfunction "C_K") (pintype "passive"))
    )
    (net (code "267") (name "unconnected-(S74-PadA)") (class "Default")
      (node (ref "S74") (pin "A") (pinfunction "A_A") (pintype "passive"))
    )
    (net (code "268") (name "unconnected-(S75-C-PadK)") (class "Default")
      (node (ref "S75") (pin "K") (pinfunction "C_K") (pintype "passive"))
    )
    (net (code "269") (name "unconnected-(S75-PadA)") (class "Default")
      (node (ref "S75") (pin "A") (pinfunction "A_A") (pintype "passive"))
    )
    (net (code "270") (name "unconnected-(S76-C-PadK)") (class "Default")
      (node (ref "S76") (pin "K") (pinfunction "C_K") (pintype "passive"))
    )
    (net (code "271") (name "unconnected-(S76-PadA)") (class "Default")
      (node (ref "S76") (pin "A") (pinfunction "A_A") (pintype "passive"))
    )
    (net (code "272") (name "unconnected-(S77-C-PadK)") (class "Default")
      (node (ref "S77") (pin "K") (pinfunction "C_K") (pintype "passive"))
    )
    (net (code "273") (name "unconnected-(S77-PadA)") (class "Default")
      (node (ref "S77") (pin "A") (pinfunction "A_A") (pintype "passive"))
    )
    (net (code "274") (name "unconnected-(S78-C-PadK)") (class "Default")
      (node (ref "S78") (pin "K") (pinfunction "C_K") (pintype "passive"))
    )
    (net (code "275") (name "unconnected-(S78-PadA)") (class "Default")
      (node (ref "S78") (pin "A") (pinfunction "A_A") (pintype "passive"))
    )
    (net (code "276") (name "unconnected-(S79-C-PadK)") (class "Default")
      (node (ref "S79") (pin "K") (pinfunction "C_K") (pintype "passive"))
    )
    (net (code "277") (name "unconnected-(S79-PadA)") (class "Default")
      (node (ref "S79") (pin "A") (pinfunction "A_A") (pintype "passive"))
    )
    (net (code "278") (name "unconnected-(U$1-A8SBU1-PadA8)") (class "Default")
      (node (ref "U$1") (pin "A8") (pinfunction "A8SBU1_A8") (pintype "bidirectional"))
    )
    (net (code "279") (name "unconnected-(U$1-B8SBU2-PadB8)") (class "Default")
      (node (ref "U$1") (pin "B8") (pinfunction "B8SBU2_B8") (pintype "bidirectional"))
    )
  )
)
